# SCH___2022-10-11.net
KiCad netlist of a schematic drawn in EasyEDA
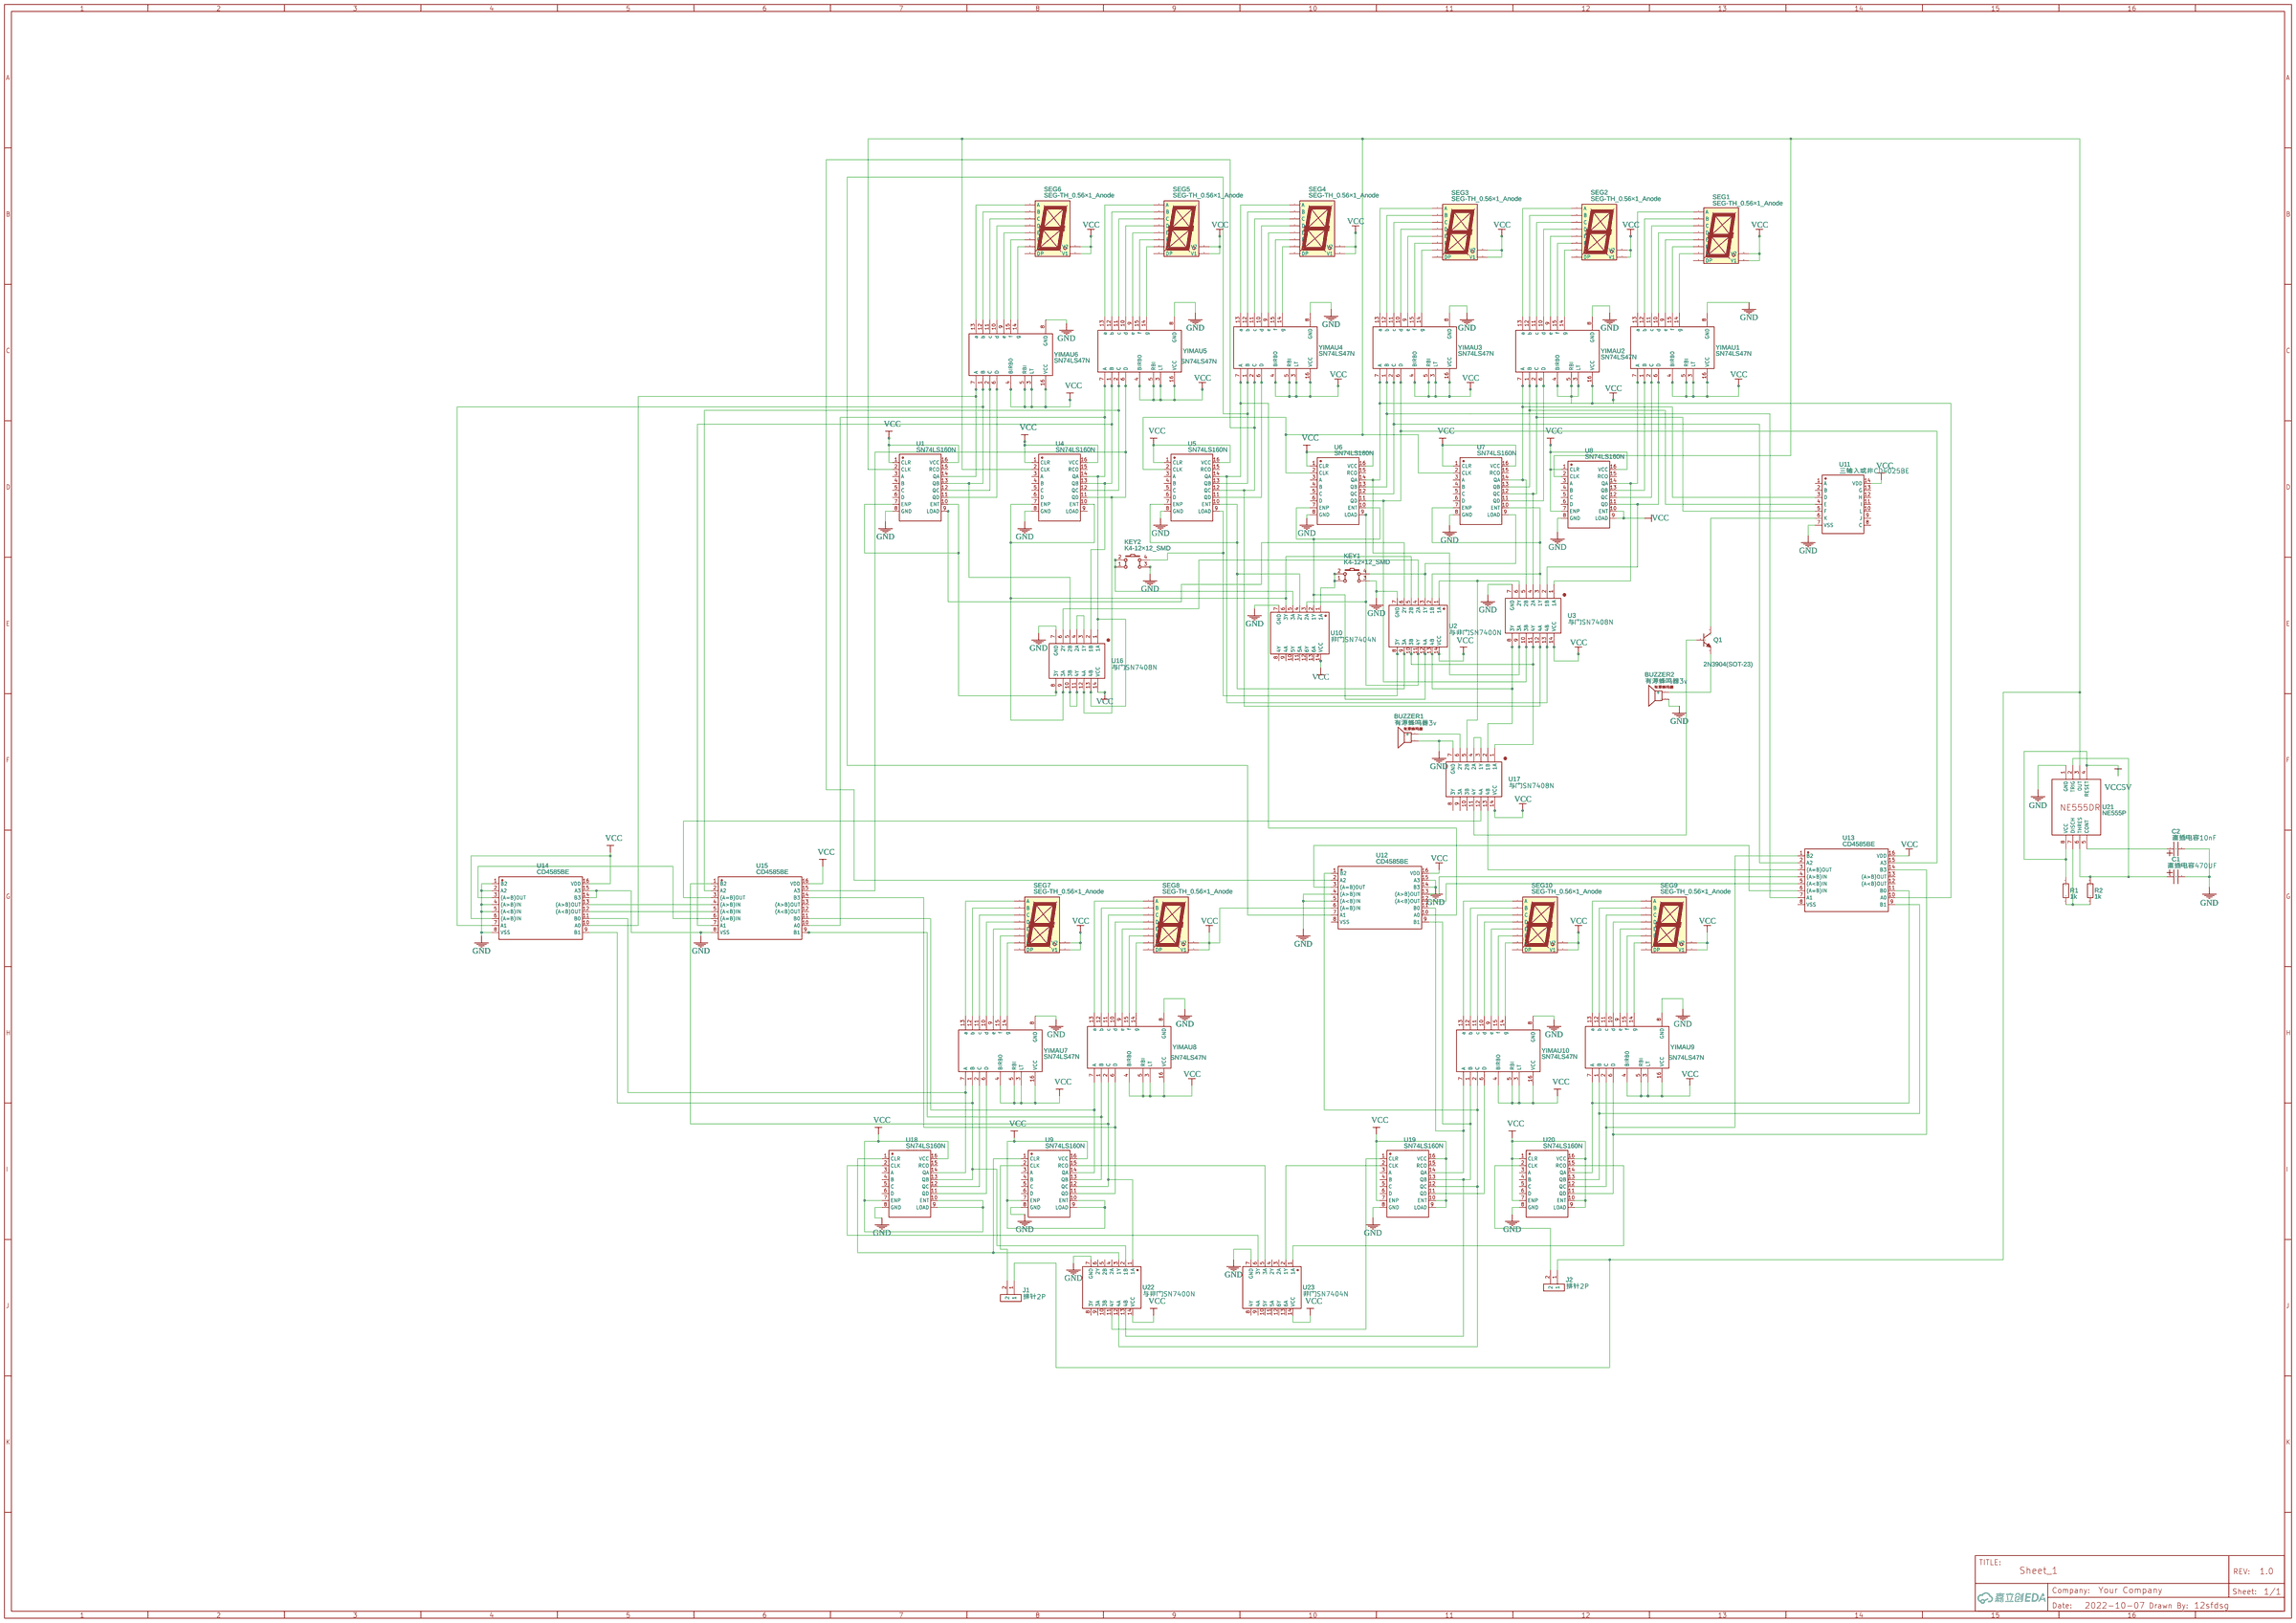
[diagram p0: schematic sheet]

(export (version "E")
  (design (tool "Eeschema 10.0.6"))
  (components
    (comp (ref "BUZZER1")
      (value "有源蜂鸣器3v")
      (fields (field (name "BOM_Manufacturer Part") "TMB12A12") (field (name "BOM_Supplier Part") "C96079"))
      (libsource (lib "") (part "有源蜂鸣器3v"))
    )
    (comp (ref "BUZZER2")
      (value "有源蜂鸣器3v")
      (fields (field (name "BOM_Manufacturer Part") "TMB12A12") (field (name "BOM_Supplier Part") "C96079"))
      (libsource (lib "") (part "有源蜂鸣器3v"))
    )
    (comp (ref "C1") (value "直插电容470UF") (libsource (lib "") (part "直插电容470UF")))
    (comp (ref "C2") (value "直插电容10nF") (libsource (lib "") (part "直插电容470UF_1")))
    (comp (ref "J1") (value "排针2P") (libsource (lib "") (part "排针2P")))
    (comp (ref "J2") (value "排针2P") (libsource (lib "") (part "排针2P")))
    (comp (ref "KEY1")
      (value "K4-12×12_SMD")
      (fields
        (field (name "BOM_Manufacturer Part") "K2-1103SP-E4SW-04")
        (field (name "BOM_Supplier Part") "C136697")
      )
      (libsource (lib "") (part "K4-12×12_SMD"))
    )
    (comp (ref "KEY2")
      (value "K4-12×12_SMD")
      (fields
        (field (name "BOM_Manufacturer Part") "K2-1103SP-E4SW-04")
        (field (name "BOM_Supplier Part") "C136697")
      )
      (libsource (lib "") (part "K4-12×12_SMD"))
    )
    (comp (ref "Q1")
      (value "2N3904(SOT-23)")
      (fields
        (field (name "BOM_Manufacturer Part") "2n3904S-RTK/PS")
        (field (name "BOM_Supplier Part") "C18536")
      )
      (libsource (lib "") (part "2N3904(SOT-23)"))
    )
    (comp (ref "R1")
      (value "1k")
      (fields
        (field (name "BOM_Manufacturer Part") "CFR0W4J0681A50")
        (field (name "BOM_Supplier Part") "C70784")
      )
      (libsource (lib "") (part "直插电阻"))
    )
    (comp (ref "R2")
      (value "1k")
      (fields
        (field (name "BOM_Manufacturer Part") "CFR0W4J0681A50")
        (field (name "BOM_Supplier Part") "C70784")
      )
      (libsource (lib "") (part "直插电阻"))
    )
    (comp (ref "SEG1")
      (value "SEG-TH_0.56×1_Anode")
      (fields (field (name "BOM_Supplier Part") "C8092"))
      (libsource (lib "") (part "SEG-TH_0.56×1_Anode"))
    )
    (comp (ref "SEG2")
      (value "SEG-TH_0.56×1_Anode")
      (fields (field (name "BOM_Supplier Part") "C8092"))
      (libsource (lib "") (part "SEG-TH_0.56×1_Anode"))
    )
    (comp (ref "SEG3")
      (value "SEG-TH_0.56×1_Anode")
      (fields (field (name "BOM_Supplier Part") "C8092"))
      (libsource (lib "") (part "SEG-TH_0.56×1_Anode"))
    )
    (comp (ref "SEG4")
      (value "SEG-TH_0.56×1_Anode")
      (fields (field (name "BOM_Supplier Part") "C8092"))
      (libsource (lib "") (part "SEG-TH_0.56×1_Anode"))
    )
    (comp (ref "SEG5")
      (value "SEG-TH_0.56×1_Anode")
      (fields (field (name "BOM_Supplier Part") "C8092"))
      (libsource (lib "") (part "SEG-TH_0.56×1_Anode"))
    )
    (comp (ref "SEG6")
      (value "SEG-TH_0.56×1_Anode")
      (fields (field (name "BOM_Supplier Part") "C8092"))
      (libsource (lib "") (part "SEG-TH_0.56×1_Anode"))
    )
    (comp (ref "SEG7")
      (value "SEG-TH_0.56×1_Anode")
      (fields (field (name "BOM_Supplier Part") "C8092"))
      (libsource (lib "") (part "SEG-TH_0.56×1_Anode"))
    )
    (comp (ref "SEG8")
      (value "SEG-TH_0.56×1_Anode")
      (fields (field (name "BOM_Supplier Part") "C8092"))
      (libsource (lib "") (part "SEG-TH_0.56×1_Anode"))
    )
    (comp (ref "SEG9")
      (value "SEG-TH_0.56×1_Anode")
      (fields (field (name "BOM_Supplier Part") "C8092"))
      (libsource (lib "") (part "SEG-TH_0.56×1_Anode"))
    )
    (comp (ref "SEG10")
      (value "SEG-TH_0.56×1_Anode")
      (fields (field (name "BOM_Supplier Part") "C8092"))
      (libsource (lib "") (part "SEG-TH_0.56×1_Anode"))
    )
    (comp (ref "U1")
      (value "SN74LS160N")
      (fields
        (field (name "BOM_Manufacturer Part") "CC0805JRNPO9BN821")
        (field (name "BOM_Supplier Part") "C113834")
      )
      (libsource (lib "") (part "SN74LS160N"))
    )
    (comp (ref "U2") (value "与非门SN7400N") (libsource (lib "") (part "SN7400N")))
    (comp (ref "U3") (value "与门SN7408N") (libsource (lib "") (part "SN7408N")))
    (comp (ref "U4")
      (value "SN74LS160N")
      (fields
        (field (name "BOM_Manufacturer Part") "CC0805JRNPO9BN821")
        (field (name "BOM_Supplier Part") "C113834")
      )
      (libsource (lib "") (part "SN74LS160N"))
    )
    (comp (ref "U5")
      (value "SN74LS160N")
      (fields
        (field (name "BOM_Manufacturer Part") "CC0805JRNPO9BN821")
        (field (name "BOM_Supplier Part") "C113834")
      )
      (libsource (lib "") (part "SN74LS160N"))
    )
    (comp (ref "U6")
      (value "SN74LS160N")
      (fields
        (field (name "BOM_Manufacturer Part") "CC0805JRNPO9BN821")
        (field (name "BOM_Supplier Part") "C113834")
      )
      (libsource (lib "") (part "SN74LS160N"))
    )
    (comp (ref "U7")
      (value "SN74LS160N")
      (fields
        (field (name "BOM_Manufacturer Part") "CC0805JRNPO9BN821")
        (field (name "BOM_Supplier Part") "C113834")
      )
      (libsource (lib "") (part "SN74LS160N"))
    )
    (comp (ref "U8")
      (value "SN74LS160N")
      (fields
        (field (name "BOM_Manufacturer Part") "CC0805JRNPO9BN821")
        (field (name "BOM_Supplier Part") "C113834")
      )
      (libsource (lib "") (part "SN74LS160N"))
    )
    (comp (ref "U9")
      (value "SN74LS160N")
      (fields
        (field (name "BOM_Manufacturer Part") "CC0805JRNPO9BN821")
        (field (name "BOM_Supplier Part") "C113834")
      )
      (libsource (lib "") (part "SN74LS160N"))
    )
    (comp (ref "U10") (value "非门SN7404N") (libsource (lib "") (part "SN7404N")))
    (comp (ref "U11")
      (value "三输入或非CD4025BE")
      (fields (field (name "BOM_Manufacturer Part") "CD4025BE") (field (name "BOM_Supplier Part") "C28214"))
      (libsource (lib "") (part "CD4025BE"))
    )
    (comp (ref "U12")
      (value "CD4585BE")
      (fields (field (name "BOM_Supplier Part") "C31466"))
      (libsource (lib "") (part "CD4585BE"))
    )
    (comp (ref "U13")
      (value "CD4585BE")
      (fields (field (name "BOM_Supplier Part") "C31466"))
      (libsource (lib "") (part "CD4585BE"))
    )
    (comp (ref "U14")
      (value "CD4585BE")
      (fields (field (name "BOM_Supplier Part") "C31466"))
      (libsource (lib "") (part "CD4585BE"))
    )
    (comp (ref "U15")
      (value "CD4585BE")
      (fields (field (name "BOM_Supplier Part") "C31466"))
      (libsource (lib "") (part "CD4585BE"))
    )
    (comp (ref "U16") (value "与门SN7408N") (libsource (lib "") (part "SN7408N")))
    (comp (ref "U17") (value "与门SN7408N") (libsource (lib "") (part "SN7408N")))
    (comp (ref "U18")
      (value "SN74LS160N")
      (fields
        (field (name "BOM_Manufacturer Part") "CC0805JRNPO9BN821")
        (field (name "BOM_Supplier Part") "C113834")
      )
      (libsource (lib "") (part "SN74LS160N"))
    )
    (comp (ref "U19")
      (value "SN74LS160N")
      (fields
        (field (name "BOM_Manufacturer Part") "CC0805JRNPO9BN821")
        (field (name "BOM_Supplier Part") "C113834")
      )
      (libsource (lib "") (part "SN74LS160N"))
    )
    (comp (ref "U20")
      (value "SN74LS160N")
      (fields
        (field (name "BOM_Manufacturer Part") "CC0805JRNPO9BN821")
        (field (name "BOM_Supplier Part") "C113834")
      )
      (libsource (lib "") (part "SN74LS160N"))
    )
    (comp (ref "U21") (value "NE555P") (libsource (lib "") (part "NE555P")))
    (comp (ref "U22") (value "与非门SN7400N") (libsource (lib "") (part "SN7400N")))
    (comp (ref "U23") (value "非门SN7404N") (libsource (lib "") (part "SN7404N")))
    (comp (ref "YIMAU1")
      (value "SN74LS47N")
      (fields (field (name "BOM_Supplier Part") "C129379"))
      (libsource (lib "") (part "Unknown_2395_-1825"))
    )
    (comp (ref "YIMAU2")
      (value "SN74LS47N")
      (fields (field (name "BOM_Supplier Part") "C129379"))
      (libsource (lib "") (part "Unknown_2230_-1820"))
    )
    (comp (ref "YIMAU3")
      (value "SN74LS47N")
      (fields (field (name "BOM_Supplier Part") "C129379"))
      (libsource (lib "") (part "Unknown_2025_-1825"))
    )
    (comp (ref "YIMAU4")
      (value "SN74LS47N")
      (fields (field (name "BOM_Supplier Part") "C129379"))
      (libsource (lib "") (part "Unknown_1825_-1825"))
    )
    (comp (ref "YIMAU5")
      (value "SN74LS47N")
      (fields (field (name "BOM_Supplier Part") "C129379"))
      (libsource (lib "") (part "Unknown_1630_-1820"))
    )
    (comp (ref "YIMAU6")
      (value "SN74LS47N")
      (fields (field (name "BOM_Supplier Part") "C129379"))
      (libsource (lib "") (part "Unknown_1445_-1815"))
    )
    (comp (ref "YIMAU7")
      (value "SN74LS47N")
      (fields (field (name "BOM_Supplier Part") "C129379"))
      (libsource (lib "") (part "Unknown_1430_-815"))
    )
    (comp (ref "YIMAU8")
      (value "SN74LS47N")
      (fields (field (name "BOM_Supplier Part") "C129379"))
      (libsource (lib "") (part "Unknown_1615_-820"))
    )
    (comp (ref "YIMAU9")
      (value "SN74LS47N")
      (fields (field (name "BOM_Supplier Part") "C129379"))
      (libsource (lib "") (part "Unknown_2330_-820"))
    )
    (comp (ref "YIMAU10")
      (value "SN74LS47N")
      (fields (field (name "BOM_Supplier Part") "C129379"))
      (libsource (lib "") (part "Unknown_2145_-815"))
    )
  )
  (nets
    (net (code "1") (name "GND") (class "Default")
      (node (ref "BUZZER1") (pin "-") (pinfunction "-_-") (pintype "unspecified"))
      (node (ref "BUZZER2") (pin "-") (pinfunction "-_-") (pintype "unspecified"))
      (node (ref "C1") (pin "2") (pinfunction "2_2") (pintype "unspecified"))
      (node (ref "C2") (pin "2") (pinfunction "2_2") (pintype "unspecified"))
      (node (ref "KEY1") (pin "3") (pinfunction "3_3") (pintype "unspecified"))
      (node (ref "KEY2") (pin "3") (pinfunction "3_3") (pintype "unspecified"))
      (node (ref "U1") (pin "8") (pinfunction "GND_8") (pintype "unspecified"))
      (node (ref "U10") (pin "7") (pinfunction "GND_7") (pintype "unspecified"))
      (node (ref "U11") (pin "7") (pinfunction "VSS_7") (pintype "unspecified"))
      (node (ref "U12") (pin "14") (pinfunction "B3_14") (pintype "unspecified"))
      (node (ref "U12") (pin "15") (pinfunction "A3_15") (pintype "unspecified"))
      (node (ref "U12") (pin "4") (pinfunction "(A>B)IN_4") (pintype "unspecified"))
      (node (ref "U12") (pin "5") (pinfunction "(A<B)IN_5") (pintype "unspecified"))
      (node (ref "U14") (pin "1") (pinfunction "B2_1") (pintype "unspecified"))
      (node (ref "U14") (pin "14") (pinfunction "B3_14") (pintype "unspecified"))
      (node (ref "U14") (pin "15") (pinfunction "A3_15") (pintype "unspecified"))
      (node (ref "U14") (pin "2") (pinfunction "A2_2") (pintype "unspecified"))
      (node (ref "U14") (pin "4") (pinfunction "(A>B)IN_4") (pintype "unspecified"))
      (node (ref "U14") (pin "5") (pinfunction "(A<B)IN_5") (pintype "unspecified"))
      (node (ref "U14") (pin "8") (pinfunction "VSS_8") (pintype "unspecified"))
      (node (ref "U15") (pin "8") (pinfunction "VSS_8") (pintype "unspecified"))
      (node (ref "U16") (pin "7") (pinfunction "GND_7") (pintype "unspecified"))
      (node (ref "U17") (pin "7") (pinfunction "GND_7") (pintype "unspecified"))
      (node (ref "U18") (pin "8") (pinfunction "GND_8") (pintype "unspecified"))
      (node (ref "U19") (pin "8") (pinfunction "GND_8") (pintype "unspecified"))
      (node (ref "U2") (pin "7") (pinfunction "GND_7") (pintype "unspecified"))
      (node (ref "U20") (pin "8") (pinfunction "GND_8") (pintype "unspecified"))
      (node (ref "U21") (pin "1") (pinfunction "GND_1") (pintype "unspecified"))
      (node (ref "U22") (pin "7") (pinfunction "GND_7") (pintype "unspecified"))
      (node (ref "U23") (pin "7") (pinfunction "GND_7") (pintype "unspecified"))
      (node (ref "U3") (pin "7") (pinfunction "GND_7") (pintype "unspecified"))
      (node (ref "U4") (pin "8") (pinfunction "GND_8") (pintype "unspecified"))
      (node (ref "U5") (pin "8") (pinfunction "GND_8") (pintype "unspecified"))
      (node (ref "U6") (pin "8") (pinfunction "GND_8") (pintype "unspecified"))
      (node (ref "U7") (pin "8") (pinfunction "GND_8") (pintype "unspecified"))
      (node (ref "U8") (pin "8") (pinfunction "GND_8") (pintype "unspecified"))
      (node (ref "U9") (pin "8") (pinfunction "GND_8") (pintype "unspecified"))
      (node (ref "YIMAU1") (pin "8") (pinfunction "GND_8") (pintype "passive"))
      (node (ref "YIMAU10") (pin "8") (pinfunction "GND_8") (pintype "passive"))
      (node (ref "YIMAU2") (pin "8") (pinfunction "GND_8") (pintype "passive"))
      (node (ref "YIMAU3") (pin "8") (pinfunction "GND_8") (pintype "passive"))
      (node (ref "YIMAU4") (pin "8") (pinfunction "GND_8") (pintype "passive"))
      (node (ref "YIMAU5") (pin "8") (pinfunction "GND_8") (pintype "passive"))
      (node (ref "YIMAU6") (pin "8") (pinfunction "GND_8") (pintype "passive"))
      (node (ref "YIMAU7") (pin "8") (pinfunction "GND_8") (pintype "passive"))
      (node (ref "YIMAU8") (pin "8") (pinfunction "GND_8") (pintype "passive"))
      (node (ref "YIMAU9") (pin "8") (pinfunction "GND_8") (pintype "passive"))
    )
    (net (code "2") (name "Net-(Q1-B)") (class "Default")
      (node (ref "Q1") (pin "2") (pinfunction "B_2") (pintype "input"))
      (node (ref "U17") (pin "11") (pinfunction "4Y_11") (pintype "unspecified"))
    )
    (net (code "3") (name "Net-(Q1-C)") (class "Default")
      (node (ref "Q1") (pin "3") (pinfunction "C_3") (pintype "input"))
      (node (ref "U11") (pin "6") (pinfunction "K_6") (pintype "unspecified"))
    )
    (net (code "4") (name "Net-(Q1-E)") (class "Default")
      (node (ref "BUZZER2") (pin "+") (pinfunction "+_+") (pintype "unspecified"))
      (node (ref "Q1") (pin "1") (pinfunction "E_1") (pintype "input"))
    )
    (net (code "5") (name "Net-(SEG1-A)") (class "Default")
      (node (ref "SEG1") (pin "7") (pinfunction "A_7") (pintype "unspecified"))
      (node (ref "YIMAU1") (pin "13") (pinfunction "a_13") (pintype "unspecified"))
    )
    (net (code "6") (name "Net-(SEG1-B)") (class "Default")
      (node (ref "SEG1") (pin "6") (pinfunction "B_6") (pintype "unspecified"))
      (node (ref "YIMAU1") (pin "12") (pinfunction "b_12") (pintype "unspecified"))
    )
    (net (code "7") (name "Net-(SEG1-C)") (class "Default")
      (node (ref "SEG1") (pin "4") (pinfunction "C_4") (pintype "unspecified"))
      (node (ref "YIMAU1") (pin "11") (pinfunction "c_11") (pintype "unspecified"))
    )
    (net (code "8") (name "Net-(SEG1-D)") (class "Default")
      (node (ref "SEG1") (pin "2") (pinfunction "D_2") (pintype "unspecified"))
      (node (ref "YIMAU1") (pin "10") (pinfunction "d_10") (pintype "unspecified"))
    )
    (net (code "9") (name "Net-(SEG1-E)") (class "Default")
      (node (ref "SEG1") (pin "1") (pinfunction "E_1") (pintype "unspecified"))
      (node (ref "YIMAU1") (pin "9") (pinfunction "e_9") (pintype "unspecified"))
    )
    (net (code "10") (name "Net-(SEG1-F)") (class "Default")
      (node (ref "SEG1") (pin "9") (pinfunction "F_9") (pintype "unspecified"))
      (node (ref "YIMAU1") (pin "15") (pinfunction "f_15") (pintype "unspecified"))
    )
    (net (code "11") (name "Net-(SEG1-G)") (class "Default")
      (node (ref "SEG1") (pin "10") (pinfunction "G_10") (pintype "unspecified"))
      (node (ref "YIMAU1") (pin "14") (pinfunction "g_14") (pintype "unspecified"))
    )
    (net (code "12") (name "Net-(SEG2-A)") (class "Default")
      (node (ref "SEG2") (pin "7") (pinfunction "A_7") (pintype "unspecified"))
      (node (ref "YIMAU2") (pin "13") (pinfunction "a_13") (pintype "unspecified"))
    )
    (net (code "13") (name "Net-(SEG2-B)") (class "Default")
      (node (ref "SEG2") (pin "6") (pinfunction "B_6") (pintype "unspecified"))
      (node (ref "YIMAU2") (pin "12") (pinfunction "b_12") (pintype "unspecified"))
    )
    (net (code "14") (name "Net-(SEG2-C)") (class "Default")
      (node (ref "SEG2") (pin "4") (pinfunction "C_4") (pintype "unspecified"))
      (node (ref "YIMAU2") (pin "11") (pinfunction "c_11") (pintype "unspecified"))
    )
    (net (code "15") (name "Net-(SEG2-D)") (class "Default")
      (node (ref "SEG2") (pin "2") (pinfunction "D_2") (pintype "unspecified"))
      (node (ref "YIMAU2") (pin "10") (pinfunction "d_10") (pintype "unspecified"))
    )
    (net (code "16") (name "Net-(SEG2-E)") (class "Default")
      (node (ref "SEG2") (pin "1") (pinfunction "E_1") (pintype "unspecified"))
      (node (ref "YIMAU2") (pin "9") (pinfunction "e_9") (pintype "unspecified"))
    )
    (net (code "17") (name "Net-(SEG2-F)") (class "Default")
      (node (ref "SEG2") (pin "9") (pinfunction "F_9") (pintype "unspecified"))
      (node (ref "YIMAU2") (pin "15") (pinfunction "f_15") (pintype "unspecified"))
    )
    (net (code "18") (name "Net-(SEG2-G)") (class "Default")
      (node (ref "SEG2") (pin "10") (pinfunction "G_10") (pintype "unspecified"))
      (node (ref "YIMAU2") (pin "14") (pinfunction "g_14") (pintype "unspecified"))
    )
    (net (code "19") (name "Net-(SEG3-A)") (class "Default")
      (node (ref "SEG3") (pin "7") (pinfunction "A_7") (pintype "unspecified"))
      (node (ref "YIMAU3") (pin "13") (pinfunction "a_13") (pintype "unspecified"))
    )
    (net (code "20") (name "Net-(SEG3-B)") (class "Default")
      (node (ref "SEG3") (pin "6") (pinfunction "B_6") (pintype "unspecified"))
      (node (ref "YIMAU3") (pin "12") (pinfunction "b_12") (pintype "unspecified"))
    )
    (net (code "21") (name "Net-(SEG3-C)") (class "Default")
      (node (ref "SEG3") (pin "4") (pinfunction "C_4") (pintype "unspecified"))
      (node (ref "YIMAU3") (pin "11") (pinfunction "c_11") (pintype "unspecified"))
    )
    (net (code "22") (name "Net-(SEG3-D)") (class "Default")
      (node (ref "SEG3") (pin "2") (pinfunction "D_2") (pintype "unspecified"))
      (node (ref "YIMAU3") (pin "10") (pinfunction "d_10") (pintype "unspecified"))
    )
    (net (code "23") (name "Net-(SEG3-E)") (class "Default")
      (node (ref "SEG3") (pin "1") (pinfunction "E_1") (pintype "unspecified"))
      (node (ref "YIMAU3") (pin "9") (pinfunction "e_9") (pintype "unspecified"))
    )
    (net (code "24") (name "Net-(SEG3-F)") (class "Default")
      (node (ref "SEG3") (pin "9") (pinfunction "F_9") (pintype "unspecified"))
      (node (ref "YIMAU3") (pin "15") (pinfunction "f_15") (pintype "unspecified"))
    )
    (net (code "25") (name "Net-(SEG3-G)") (class "Default")
      (node (ref "SEG3") (pin "10") (pinfunction "G_10") (pintype "unspecified"))
      (node (ref "YIMAU3") (pin "14") (pinfunction "g_14") (pintype "unspecified"))
    )
    (net (code "26") (name "Net-(SEG4-A)") (class "Default")
      (node (ref "SEG4") (pin "7") (pinfunction "A_7") (pintype "unspecified"))
      (node (ref "YIMAU4") (pin "13") (pinfunction "a_13") (pintype "unspecified"))
    )
    (net (code "27") (name "Net-(SEG4-B)") (class "Default")
      (node (ref "SEG4") (pin "6") (pinfunction "B_6") (pintype "unspecified"))
      (node (ref "YIMAU4") (pin "12") (pinfunction "b_12") (pintype "unspecified"))
    )
    (net (code "28") (name "Net-(SEG4-C)") (class "Default")
      (node (ref "SEG4") (pin "4") (pinfunction "C_4") (pintype "unspecified"))
      (node (ref "YIMAU4") (pin "11") (pinfunction "c_11") (pintype "unspecified"))
    )
    (net (code "29") (name "Net-(SEG4-D)") (class "Default")
      (node (ref "SEG4") (pin "2") (pinfunction "D_2") (pintype "unspecified"))
      (node (ref "YIMAU4") (pin "10") (pinfunction "d_10") (pintype "unspecified"))
    )
    (net (code "30") (name "Net-(SEG4-E)") (class "Default")
      (node (ref "SEG4") (pin "1") (pinfunction "E_1") (pintype "unspecified"))
      (node (ref "YIMAU4") (pin "9") (pinfunction "e_9") (pintype "unspecified"))
    )
    (net (code "31") (name "Net-(SEG4-F)") (class "Default")
      (node (ref "SEG4") (pin "9") (pinfunction "F_9") (pintype "unspecified"))
      (node (ref "YIMAU4") (pin "15") (pinfunction "f_15") (pintype "unspecified"))
    )
    (net (code "32") (name "Net-(SEG4-G)") (class "Default")
      (node (ref "SEG4") (pin "10") (pinfunction "G_10") (pintype "unspecified"))
      (node (ref "YIMAU4") (pin "14") (pinfunction "g_14") (pintype "unspecified"))
    )
    (net (code "33") (name "Net-(SEG5-A)") (class "Default")
      (node (ref "SEG5") (pin "7") (pinfunction "A_7") (pintype "unspecified"))
      (node (ref "YIMAU5") (pin "13") (pinfunction "a_13") (pintype "unspecified"))
    )
    (net (code "34") (name "Net-(SEG5-B)") (class "Default")
      (node (ref "SEG5") (pin "6") (pinfunction "B_6") (pintype "unspecified"))
      (node (ref "YIMAU5") (pin "12") (pinfunction "b_12") (pintype "unspecified"))
    )
    (net (code "35") (name "Net-(SEG5-C)") (class "Default")
      (node (ref "SEG5") (pin "4") (pinfunction "C_4") (pintype "unspecified"))
      (node (ref "YIMAU5") (pin "11") (pinfunction "c_11") (pintype "unspecified"))
    )
    (net (code "36") (name "Net-(SEG5-D)") (class "Default")
      (node (ref "SEG5") (pin "2") (pinfunction "D_2") (pintype "unspecified"))
      (node (ref "YIMAU5") (pin "10") (pinfunction "d_10") (pintype "unspecified"))
    )
    (net (code "37") (name "Net-(SEG5-E)") (class "Default")
      (node (ref "SEG5") (pin "1") (pinfunction "E_1") (pintype "unspecified"))
      (node (ref "YIMAU5") (pin "9") (pinfunction "e_9") (pintype "unspecified"))
    )
    (net (code "38") (name "Net-(SEG5-F)") (class "Default")
      (node (ref "SEG5") (pin "9") (pinfunction "F_9") (pintype "unspecified"))
      (node (ref "YIMAU5") (pin "15") (pinfunction "f_15") (pintype "unspecified"))
    )
    (net (code "39") (name "Net-(SEG5-G)") (class "Default")
      (node (ref "SEG5") (pin "10") (pinfunction "G_10") (pintype "unspecified"))
      (node (ref "YIMAU5") (pin "14") (pinfunction "g_14") (pintype "unspecified"))
    )
    (net (code "40") (name "Net-(SEG6-A)") (class "Default")
      (node (ref "SEG6") (pin "7") (pinfunction "A_7") (pintype "unspecified"))
      (node (ref "YIMAU6") (pin "13") (pinfunction "a_13") (pintype "unspecified"))
    )
    (net (code "41") (name "Net-(SEG6-B)") (class "Default")
      (node (ref "SEG6") (pin "6") (pinfunction "B_6") (pintype "unspecified"))
      (node (ref "YIMAU6") (pin "12") (pinfunction "b_12") (pintype "unspecified"))
    )
    (net (code "42") (name "Net-(SEG6-C)") (class "Default")
      (node (ref "SEG6") (pin "4") (pinfunction "C_4") (pintype "unspecified"))
      (node (ref "YIMAU6") (pin "11") (pinfunction "c_11") (pintype "unspecified"))
    )
    (net (code "43") (name "Net-(SEG6-D)") (class "Default")
      (node (ref "SEG6") (pin "2") (pinfunction "D_2") (pintype "unspecified"))
      (node (ref "YIMAU6") (pin "10") (pinfunction "d_10") (pintype "unspecified"))
    )
    (net (code "44") (name "Net-(SEG6-E)") (class "Default")
      (node (ref "SEG6") (pin "1") (pinfunction "E_1") (pintype "unspecified"))
      (node (ref "YIMAU6") (pin "9") (pinfunction "e_9") (pintype "unspecified"))
    )
    (net (code "45") (name "Net-(SEG6-F)") (class "Default")
      (node (ref "SEG6") (pin "9") (pinfunction "F_9") (pintype "unspecified"))
      (node (ref "YIMAU6") (pin "15") (pinfunction "f_15") (pintype "unspecified"))
    )
    (net (code "46") (name "Net-(SEG6-G)") (class "Default")
      (node (ref "SEG6") (pin "10") (pinfunction "G_10") (pintype "unspecified"))
      (node (ref "YIMAU6") (pin "14") (pinfunction "g_14") (pintype "unspecified"))
    )
    (net (code "47") (name "Net-(SEG7-A)") (class "Default")
      (node (ref "SEG7") (pin "7") (pinfunction "A_7") (pintype "unspecified"))
      (node (ref "YIMAU7") (pin "13") (pinfunction "a_13") (pintype "unspecified"))
    )
    (net (code "48") (name "Net-(SEG7-B)") (class "Default")
      (node (ref "SEG7") (pin "6") (pinfunction "B_6") (pintype "unspecified"))
      (node (ref "YIMAU7") (pin "12") (pinfunction "b_12") (pintype "unspecified"))
    )
    (net (code "49") (name "Net-(SEG7-C)") (class "Default")
      (node (ref "SEG7") (pin "4") (pinfunction "C_4") (pintype "unspecified"))
      (node (ref "YIMAU7") (pin "11") (pinfunction "c_11") (pintype "unspecified"))
    )
    (net (code "50") (name "Net-(SEG7-D)") (class "Default")
      (node (ref "SEG7") (pin "2") (pinfunction "D_2") (pintype "unspecified"))
      (node (ref "YIMAU7") (pin "10") (pinfunction "d_10") (pintype "unspecified"))
    )
    (net (code "51") (name "Net-(SEG7-E)") (class "Default")
      (node (ref "SEG7") (pin "1") (pinfunction "E_1") (pintype "unspecified"))
      (node (ref "YIMAU7") (pin "9") (pinfunction "e_9") (pintype "unspecified"))
    )
    (net (code "52") (name "Net-(SEG7-F)") (class "Default")
      (node (ref "SEG7") (pin "9") (pinfunction "F_9") (pintype "unspecified"))
      (node (ref "YIMAU7") (pin "15") (pinfunction "f_15") (pintype "unspecified"))
    )
    (net (code "53") (name "Net-(SEG7-G)") (class "Default")
      (node (ref "SEG7") (pin "10") (pinfunction "G_10") (pintype "unspecified"))
      (node (ref "YIMAU7") (pin "14") (pinfunction "g_14") (pintype "unspecified"))
    )
    (net (code "54") (name "Net-(SEG8-A)") (class "Default")
      (node (ref "SEG8") (pin "7") (pinfunction "A_7") (pintype "unspecified"))
      (node (ref "YIMAU8") (pin "13") (pinfunction "a_13") (pintype "unspecified"))
    )
    (net (code "55") (name "Net-(SEG8-B)") (class "Default")
      (node (ref "SEG8") (pin "6") (pinfunction "B_6") (pintype "unspecified"))
      (node (ref "YIMAU8") (pin "12") (pinfunction "b_12") (pintype "unspecified"))
    )
    (net (code "56") (name "Net-(SEG8-C)") (class "Default")
      (node (ref "SEG8") (pin "4") (pinfunction "C_4") (pintype "unspecified"))
      (node (ref "YIMAU8") (pin "11") (pinfunction "c_11") (pintype "unspecified"))
    )
    (net (code "57") (name "Net-(SEG8-D)") (class "Default")
      (node (ref "SEG8") (pin "2") (pinfunction "D_2") (pintype "unspecified"))
      (node (ref "YIMAU8") (pin "10") (pinfunction "d_10") (pintype "unspecified"))
    )
    (net (code "58") (name "Net-(SEG8-E)") (class "Default")
      (node (ref "SEG8") (pin "1") (pinfunction "E_1") (pintype "unspecified"))
      (node (ref "YIMAU8") (pin "9") (pinfunction "e_9") (pintype "unspecified"))
    )
    (net (code "59") (name "Net-(SEG8-F)") (class "Default")
      (node (ref "SEG8") (pin "9") (pinfunction "F_9") (pintype "unspecified"))
      (node (ref "YIMAU8") (pin "15") (pinfunction "f_15") (pintype "unspecified"))
    )
    (net (code "60") (name "Net-(SEG8-G)") (class "Default")
      (node (ref "SEG8") (pin "10") (pinfunction "G_10") (pintype "unspecified"))
      (node (ref "YIMAU8") (pin "14") (pinfunction "g_14") (pintype "unspecified"))
    )
    (net (code "61") (name "Net-(SEG9-A)") (class "Default")
      (node (ref "SEG9") (pin "7") (pinfunction "A_7") (pintype "unspecified"))
      (node (ref "YIMAU9") (pin "13") (pinfunction "a_13") (pintype "unspecified"))
    )
    (net (code "62") (name "Net-(SEG9-B)") (class "Default")
      (node (ref "SEG9") (pin "6") (pinfunction "B_6") (pintype "unspecified"))
      (node (ref "YIMAU9") (pin "12") (pinfunction "b_12") (pintype "unspecified"))
    )
    (net (code "63") (name "Net-(SEG9-C)") (class "Default")
      (node (ref "SEG9") (pin "4") (pinfunction "C_4") (pintype "unspecified"))
      (node (ref "YIMAU9") (pin "11") (pinfunction "c_11") (pintype "unspecified"))
    )
    (net (code "64") (name "Net-(SEG9-D)") (class "Default")
      (node (ref "SEG9") (pin "2") (pinfunction "D_2") (pintype "unspecified"))
      (node (ref "YIMAU9") (pin "10") (pinfunction "d_10") (pintype "unspecified"))
    )
    (net (code "65") (name "Net-(SEG9-E)") (class "Default")
      (node (ref "SEG9") (pin "1") (pinfunction "E_1") (pintype "unspecified"))
      (node (ref "YIMAU9") (pin "9") (pinfunction "e_9") (pintype "unspecified"))
    )
    (net (code "66") (name "Net-(SEG9-F)") (class "Default")
      (node (ref "SEG9") (pin "9") (pinfunction "F_9") (pintype "unspecified"))
      (node (ref "YIMAU9") (pin "15") (pinfunction "f_15") (pintype "unspecified"))
    )
    (net (code "67") (name "Net-(SEG9-G)") (class "Default")
      (node (ref "SEG9") (pin "10") (pinfunction "G_10") (pintype "unspecified"))
      (node (ref "YIMAU9") (pin "14") (pinfunction "g_14") (pintype "unspecified"))
    )
    (net (code "68") (name "Net-(SEG10-A)") (class "Default")
      (node (ref "SEG10") (pin "7") (pinfunction "A_7") (pintype "unspecified"))
      (node (ref "YIMAU10") (pin "13") (pinfunction "a_13") (pintype "unspecified"))
    )
    (net (code "69") (name "Net-(SEG10-B)") (class "Default")
      (node (ref "SEG10") (pin "6") (pinfunction "B_6") (pintype "unspecified"))
      (node (ref "YIMAU10") (pin "12") (pinfunction "b_12") (pintype "unspecified"))
    )
    (net (code "70") (name "Net-(SEG10-C)") (class "Default")
      (node (ref "SEG10") (pin "4") (pinfunction "C_4") (pintype "unspecified"))
      (node (ref "YIMAU10") (pin "11") (pinfunction "c_11") (pintype "unspecified"))
    )
    (net (code "71") (name "Net-(SEG10-D)") (class "Default")
      (node (ref "SEG10") (pin "2") (pinfunction "D_2") (pintype "unspecified"))
      (node (ref "YIMAU10") (pin "10") (pinfunction "d_10") (pintype "unspecified"))
    )
    (net (code "72") (name "Net-(SEG10-E)") (class "Default")
      (node (ref "SEG10") (pin "1") (pinfunction "E_1") (pintype "unspecified"))
      (node (ref "YIMAU10") (pin "9") (pinfunction "e_9") (pintype "unspecified"))
    )
    (net (code "73") (name "Net-(SEG10-F)") (class "Default")
      (node (ref "SEG10") (pin "9") (pinfunction "F_9") (pintype "unspecified"))
      (node (ref "YIMAU10") (pin "15") (pinfunction "f_15") (pintype "unspecified"))
    )
    (net (code "74") (name "Net-(SEG10-G)") (class "Default")
      (node (ref "SEG10") (pin "10") (pinfunction "G_10") (pintype "unspecified"))
      (node (ref "YIMAU10") (pin "14") (pinfunction "g_14") (pintype "unspecified"))
    )
    (net (code "75") (name "Net-(U1-CLK)") (class "Default")
      (node (ref "J1") (pin "1") (pinfunction "1_1") (pintype "unspecified"))
      (node (ref "J2") (pin "1") (pinfunction "1_1") (pintype "unspecified"))
      (node (ref "U1") (pin "2") (pinfunction "CLK_2") (pintype "unspecified"))
      (node (ref "U21") (pin "3") (pinfunction "OUT_3") (pintype "unspecified"))
      (node (ref "U4") (pin "2") (pinfunction "CLK_2") (pintype "unspecified"))
      (node (ref "U5") (pin "2") (pinfunction "CLK_2") (pintype "unspecified"))
      (node (ref "U6") (pin "2") (pinfunction "CLK_2") (pintype "unspecified"))
      (node (ref "U7") (pin "2") (pinfunction "CLK_2") (pintype "unspecified"))
      (node (ref "U8") (pin "2") (pinfunction "CLK_2") (pintype "unspecified"))
    )
    (net (code "76") (name "Net-(U1-ENP)") (class "Default")
      (node (ref "U1") (pin "10") (pinfunction "ENT_10") (pintype "unspecified"))
      (node (ref "U1") (pin "7") (pinfunction "ENP_7") (pintype "unspecified"))
      (node (ref "U16") (pin "8") (pinfunction "3Y_8") (pintype "unspecified"))
    )
    (net (code "77") (name "Net-(U1-LOAD)") (class "Default")
      (node (ref "U1") (pin "9") (pinfunction "LOAD_9") (pintype "unspecified"))
      (node (ref "U2") (pin "6") (pinfunction "2Y_6") (pintype "unspecified"))
    )
    (net (code "78") (name "Net-(U1-QA)") (class "Default")
      (node (ref "U1") (pin "14") (pinfunction "QA_14") (pintype "unspecified"))
      (node (ref "U14") (pin "10") (pinfunction "A0_10") (pintype "unspecified"))
      (node (ref "YIMAU6") (pin "7") (pinfunction "A_7") (pintype "unspecified"))
    )
    (net (code "79") (name "Net-(U1-QB)") (class "Default")
      (node (ref "U1") (pin "13") (pinfunction "QB_13") (pintype "unspecified"))
      (node (ref "U14") (pin "7") (pinfunction "A1_7") (pintype "unspecified"))
      (node (ref "U16") (pin "5") (pinfunction "2B_5") (pintype "unspecified"))
      (node (ref "YIMAU6") (pin "1") (pinfunction "B_1") (pintype "unspecified"))
    )
    (net (code "80") (name "Net-(U1-QC)") (class "Default")
      (node (ref "U1") (pin "12") (pinfunction "QC_12") (pintype "unspecified"))
      (node (ref "YIMAU6") (pin "2") (pinfunction "C_2") (pintype "unspecified"))
    )
    (net (code "81") (name "Net-(U1-QD)") (class "Default")
      (node (ref "U1") (pin "11") (pinfunction "QD_11") (pintype "unspecified"))
      (node (ref "YIMAU6") (pin "6") (pinfunction "D_6") (pintype "unspecified"))
    )
    (net (code "82") (name "Net-(U2-1B)") (class "Default")
      (node (ref "U2") (pin "2") (pinfunction "1B_2") (pintype "unspecified"))
      (node (ref "U3") (pin "3") (pinfunction "1Y_3") (pintype "unspecified"))
      (node (ref "U7") (pin "10") (pinfunction "ENT_10") (pintype "unspecified"))
      (node (ref "U7") (pin "7") (pinfunction "ENP_7") (pintype "unspecified"))
    )
    (net (code "83") (name "Net-(U2-1Y)") (class "Default")
      (node (ref "KEY1") (pin "4") (pinfunction "4_4") (pintype "unspecified"))
      (node (ref "U2") (pin "3") (pinfunction "1Y_3") (pintype "unspecified"))
      (node (ref "U7") (pin "9") (pinfunction "LOAD_9") (pintype "unspecified"))
    )
    (net (code "84") (name "Net-(U2-3Y)") (class "Default")
      (node (ref "KEY2") (pin "4") (pinfunction "4_4") (pintype "unspecified"))
      (node (ref "U2") (pin "8") (pinfunction "3Y_8") (pintype "unspecified"))
      (node (ref "U5") (pin "9") (pinfunction "LOAD_9") (pintype "unspecified"))
    )
    (net (code "85") (name "Net-(U3-1A)") (class "Default")
      (node (ref "U3") (pin "1") (pinfunction "1A_1") (pintype "unspecified"))
      (node (ref "U8") (pin "14") (pinfunction "QA_14") (pintype "unspecified"))
      (node (ref "YIMAU1") (pin "7") (pinfunction "A_7") (pintype "unspecified"))
    )
    (net (code "86") (name "Net-(U3-1B)") (class "Default")
      (node (ref "U3") (pin "2") (pinfunction "1B_2") (pintype "unspecified"))
      (node (ref "U8") (pin "11") (pinfunction "QD_11") (pintype "unspecified"))
      (node (ref "YIMAU1") (pin "6") (pinfunction "D_6") (pintype "unspecified"))
    )
    (net (code "87") (name "Net-(U5-QD)") (class "Default")
      (node (ref "U5") (pin "11") (pinfunction "QD_11") (pintype "unspecified"))
      (node (ref "YIMAU4") (pin "6") (pinfunction "D_6") (pintype "unspecified"))
    )
    (net (code "88") (name "Net-(U7-QD)") (class "Default")
      (node (ref "U7") (pin "11") (pinfunction "QD_11") (pintype "unspecified"))
      (node (ref "YIMAU2") (pin "6") (pinfunction "D_6") (pintype "unspecified"))
    )
    (net (code "89") (name "Net-(U8-QB)") (class "Default")
      (node (ref "U8") (pin "13") (pinfunction "QB_13") (pintype "unspecified"))
      (node (ref "YIMAU1") (pin "1") (pinfunction "B_1") (pintype "unspecified"))
    )
    (net (code "90") (name "Net-(U8-QC)") (class "Default")
      (node (ref "U8") (pin "12") (pinfunction "QC_12") (pintype "unspecified"))
      (node (ref "YIMAU1") (pin "2") (pinfunction "C_2") (pintype "unspecified"))
    )
    (net (code "91") (name "Net-(U9-CLK)") (class "Default")
      (node (ref "J1") (pin "2") (pinfunction "2_2") (pintype "unspecified"))
      (node (ref "U9") (pin "2") (pinfunction "CLK_2") (pintype "unspecified"))
    )
    (net (code "92") (name "Net-(U10-1A)") (class "Default")
      (node (ref "KEY1") (pin "1") (pinfunction "1_1") (pintype "unspecified"))
      (node (ref "KEY1") (pin "2") (pinfunction "2_2") (pintype "unspecified"))
      (node (ref "U10") (pin "1") (pinfunction "1A_1") (pintype "unspecified"))
    )
    (net (code "93") (name "Net-(U10-1Y)") (class "Default")
      (node (ref "U10") (pin "2") (pinfunction "1Y_2") (pintype "unspecified"))
      (node (ref "U2") (pin "12") (pinfunction "4A_12") (pintype "unspecified"))
      (node (ref "U6") (pin "10") (pinfunction "ENT_10") (pintype "unspecified"))
      (node (ref "U6") (pin "7") (pinfunction "ENP_7") (pintype "unspecified"))
    )
    (net (code "94") (name "Net-(U10-2A)") (class "Default")
      (node (ref "U10") (pin "3") (pinfunction "2A_3") (pintype "unspecified"))
      (node (ref "U2") (pin "11") (pinfunction "4Y_11") (pintype "unspecified"))
      (node (ref "U6") (pin "9") (pinfunction "LOAD_9") (pintype "unspecified"))
    )
    (net (code "95") (name "Net-(U10-2Y)") (class "Default")
      (node (ref "U10") (pin "4") (pinfunction "2Y_4") (pintype "unspecified"))
      (node (ref "U2") (pin "9") (pinfunction "3A_9") (pintype "unspecified"))
      (node (ref "U5") (pin "10") (pinfunction "ENT_10") (pintype "unspecified"))
      (node (ref "U5") (pin "7") (pinfunction "ENP_7") (pintype "unspecified"))
    )
    (net (code "96") (name "Net-(U10-3A)") (class "Default")
      (node (ref "KEY2") (pin "1") (pinfunction "1_1") (pintype "unspecified"))
      (node (ref "KEY2") (pin "2") (pinfunction "2_2") (pintype "unspecified"))
      (node (ref "U10") (pin "5") (pinfunction "3A_5") (pintype "unspecified"))
    )
    (net (code "97") (name "Net-(U10-3Y)") (class "Default")
      (node (ref "U10") (pin "6") (pinfunction "3Y_6") (pintype "unspecified"))
      (node (ref "U16") (pin "9") (pinfunction "3A_9") (pintype "unspecified"))
      (node (ref "U2") (pin "5") (pinfunction "2B_5") (pintype "unspecified"))
      (node (ref "U4") (pin "10") (pinfunction "ENT_10") (pintype "unspecified"))
      (node (ref "U4") (pin "7") (pinfunction "ENP_7") (pintype "unspecified"))
    )
    (net (code "98") (name "Net-(U11-D)") (class "Default")
      (node (ref "U11") (pin "3") (pinfunction "D_3") (pintype "unspecified"))
      (node (ref "U3") (pin "5") (pinfunction "2B_5") (pintype "unspecified"))
      (node (ref "U7") (pin "14") (pinfunction "QA_14") (pintype "unspecified"))
      (node (ref "YIMAU2") (pin "7") (pinfunction "A_7") (pintype "unspecified"))
    )
    (net (code "99") (name "Net-(U11-E)") (class "Default")
      (node (ref "U11") (pin "4") (pinfunction "E_4") (pintype "unspecified"))
      (node (ref "U7") (pin "13") (pinfunction "QB_13") (pintype "unspecified"))
      (node (ref "YIMAU2") (pin "1") (pinfunction "B_1") (pintype "unspecified"))
    )
    (net (code "100") (name "Net-(U11-F)") (class "Default")
      (node (ref "U11") (pin "5") (pinfunction "F_5") (pintype "unspecified"))
      (node (ref "U3") (pin "4") (pinfunction "2A_4") (pintype "unspecified"))
      (node (ref "U7") (pin "12") (pinfunction "QC_12") (pintype "unspecified"))
      (node (ref "YIMAU2") (pin "2") (pinfunction "C_2") (pintype "unspecified"))
    )
    (net (code "101") (name "Net-(U12-(A<B)OUT)") (class "Default")
      (node (ref "U12") (pin "12") (pinfunction "(A<B)OUT_12") (pintype "unspecified"))
      (node (ref "U13") (pin "5") (pinfunction "(A<B)IN_5") (pintype "unspecified"))
    )
    (net (code "102") (name "Net-(U12-(A=B)OUT)") (class "Default")
      (node (ref "U12") (pin "3") (pinfunction "(A=B)OUT_3") (pintype "unspecified"))
      (node (ref "U13") (pin "6") (pinfunction "(A=B)IN_6") (pintype "unspecified"))
    )
    (net (code "103") (name "Net-(U12-(A>B)OUT)") (class "Default")
      (node (ref "U12") (pin "13") (pinfunction "(A>B)OUT_13") (pintype "unspecified"))
      (node (ref "U13") (pin "4") (pinfunction "(A>B)IN_4") (pintype "unspecified"))
    )
    (net (code "104") (name "Net-(U12-A0)") (class "Default")
      (node (ref "U12") (pin "10") (pinfunction "A0_10") (pintype "unspecified"))
      (node (ref "U3") (pin "13") (pinfunction "4B_13") (pintype "unspecified"))
      (node (ref "U5") (pin "14") (pinfunction "QA_14") (pintype "unspecified"))
      (node (ref "YIMAU4") (pin "7") (pinfunction "A_7") (pintype "unspecified"))
    )
    (net (code "105") (name "Net-(U12-A1)") (class "Default")
      (node (ref "U12") (pin "7") (pinfunction "A1_7") (pintype "unspecified"))
      (node (ref "U5") (pin "13") (pinfunction "QB_13") (pintype "unspecified"))
      (node (ref "YIMAU4") (pin "1") (pinfunction "B_1") (pintype "unspecified"))
    )
    (net (code "106") (name "Net-(U12-A2)") (class "Default")
      (node (ref "U12") (pin "2") (pinfunction "A2_2") (pintype "unspecified"))
      (node (ref "U3") (pin "12") (pinfunction "4A_12") (pintype "unspecified"))
      (node (ref "U5") (pin "12") (pinfunction "QC_12") (pintype "unspecified"))
      (node (ref "YIMAU4") (pin "2") (pinfunction "C_2") (pintype "unspecified"))
    )
    (net (code "107") (name "Net-(U12-B0)") (class "Default")
      (node (ref "U12") (pin "11") (pinfunction "B0_11") (pintype "unspecified"))
      (node (ref "U19") (pin "14") (pinfunction "QA_14") (pintype "unspecified"))
      (node (ref "YIMAU10") (pin "7") (pinfunction "A_7") (pintype "unspecified"))
    )
    (net (code "108") (name "Net-(U12-B1)") (class "Default")
      (node (ref "U12") (pin "9") (pinfunction "B1_9") (pintype "unspecified"))
      (node (ref "U19") (pin "13") (pinfunction "QB_13") (pintype "unspecified"))
      (node (ref "U22") (pin "13") (pinfunction "4B_13") (pintype "unspecified"))
      (node (ref "YIMAU10") (pin "1") (pinfunction "B_1") (pintype "unspecified"))
    )
    (net (code "109") (name "Net-(U12-B2)") (class "Default")
      (node (ref "U12") (pin "1") (pinfunction "B2_1") (pintype "unspecified"))
      (node (ref "U19") (pin "12") (pinfunction "QC_12") (pintype "unspecified"))
      (node (ref "U22") (pin "12") (pinfunction "4A_12") (pintype "unspecified"))
      (node (ref "YIMAU10") (pin "2") (pinfunction "C_2") (pintype "unspecified"))
    )
    (net (code "110") (name "Net-(U13-(A=B)OUT)") (class "Default")
      (node (ref "U13") (pin "3") (pinfunction "(A=B)OUT_3") (pintype "unspecified"))
      (node (ref "U17") (pin "13") (pinfunction "4B_13") (pintype "unspecified"))
    )
    (net (code "111") (name "Net-(U13-A1)") (class "Default")
      (node (ref "U13") (pin "7") (pinfunction "A1_7") (pintype "unspecified"))
      (node (ref "U6") (pin "13") (pinfunction "QB_13") (pintype "unspecified"))
      (node (ref "YIMAU3") (pin "1") (pinfunction "B_1") (pintype "unspecified"))
    )
    (net (code "112") (name "Net-(U13-A2)") (class "Default")
      (node (ref "U13") (pin "2") (pinfunction "A2_2") (pintype "unspecified"))
      (node (ref "U6") (pin "12") (pinfunction "QC_12") (pintype "unspecified"))
      (node (ref "YIMAU3") (pin "2") (pinfunction "C_2") (pintype "unspecified"))
    )
    (net (code "113") (name "Net-(U13-A3)") (class "Default")
      (node (ref "U13") (pin "15") (pinfunction "A3_15") (pintype "unspecified"))
      (node (ref "U3") (pin "10") (pinfunction "3B_10") (pintype "unspecified"))
      (node (ref "U6") (pin "11") (pinfunction "QD_11") (pintype "unspecified"))
      (node (ref "YIMAU3") (pin "6") (pinfunction "D_6") (pintype "unspecified"))
    )
    (net (code "114") (name "Net-(U13-B0)") (class "Default")
      (node (ref "U13") (pin "11") (pinfunction "B0_11") (pintype "unspecified"))
      (node (ref "U20") (pin "14") (pinfunction "QA_14") (pintype "unspecified"))
      (node (ref "YIMAU9") (pin "7") (pinfunction "A_7") (pintype "unspecified"))
    )
    (net (code "115") (name "Net-(U13-B1)") (class "Default")
      (node (ref "U13") (pin "9") (pinfunction "B1_9") (pintype "unspecified"))
      (node (ref "U20") (pin "13") (pinfunction "QB_13") (pintype "unspecified"))
      (node (ref "YIMAU9") (pin "1") (pinfunction "B_1") (pintype "unspecified"))
    )
    (net (code "116") (name "Net-(U13-B2)") (class "Default")
      (node (ref "U13") (pin "1") (pinfunction "B2_1") (pintype "unspecified"))
      (node (ref "U20") (pin "12") (pinfunction "QC_12") (pintype "unspecified"))
      (node (ref "YIMAU9") (pin "2") (pinfunction "C_2") (pintype "unspecified"))
    )
    (net (code "117") (name "Net-(U13-B3)") (class "Default")
      (node (ref "U13") (pin "14") (pinfunction "B3_14") (pintype "unspecified"))
      (node (ref "U20") (pin "11") (pinfunction "QD_11") (pintype "unspecified"))
      (node (ref "YIMAU9") (pin "6") (pinfunction "D_6") (pintype "unspecified"))
    )
    (net (code "118") (name "Net-(U14-(A<B)OUT)") (class "Default")
      (node (ref "U14") (pin "12") (pinfunction "(A<B)OUT_12") (pintype "unspecified"))
      (node (ref "U15") (pin "5") (pinfunction "(A<B)IN_5") (pintype "unspecified"))
    )
    (net (code "119") (name "Net-(U14-(A=B)OUT)") (class "Default")
      (node (ref "U14") (pin "3") (pinfunction "(A=B)OUT_3") (pintype "unspecified"))
      (node (ref "U15") (pin "6") (pinfunction "(A=B)IN_6") (pintype "unspecified"))
    )
    (net (code "120") (name "Net-(U14-(A>B)OUT)") (class "Default")
      (node (ref "U14") (pin "13") (pinfunction "(A>B)OUT_13") (pintype "unspecified"))
      (node (ref "U15") (pin "4") (pinfunction "(A>B)IN_4") (pintype "unspecified"))
    )
    (net (code "121") (name "Net-(U14-B0)") (class "Default")
      (node (ref "U14") (pin "11") (pinfunction "B0_11") (pintype "unspecified"))
      (node (ref "U18") (pin "14") (pinfunction "QA_14") (pintype "unspecified"))
      (node (ref "YIMAU7") (pin "7") (pinfunction "A_7") (pintype "unspecified"))
    )
    (net (code "122") (name "Net-(U14-B1)") (class "Default")
      (node (ref "U14") (pin "9") (pinfunction "B1_9") (pintype "unspecified"))
      (node (ref "U18") (pin "13") (pinfunction "QB_13") (pintype "unspecified"))
      (node (ref "U22") (pin "2") (pinfunction "1B_2") (pintype "unspecified"))
      (node (ref "YIMAU7") (pin "1") (pinfunction "B_1") (pintype "unspecified"))
    )
    (net (code "123") (name "Net-(U15-(A=B)OUT)") (class "Default")
      (node (ref "U15") (pin "3") (pinfunction "(A=B)OUT_3") (pintype "unspecified"))
      (node (ref "U17") (pin "12") (pinfunction "4A_12") (pintype "unspecified"))
    )
    (net (code "124") (name "Net-(U15-A0)") (class "Default")
      (node (ref "U15") (pin "10") (pinfunction "A0_10") (pintype "unspecified"))
      (node (ref "U16") (pin "1") (pinfunction "1A_1") (pintype "unspecified"))
      (node (ref "U16") (pin "13") (pinfunction "4B_13") (pintype "unspecified"))
      (node (ref "U4") (pin "14") (pinfunction "QA_14") (pintype "unspecified"))
      (node (ref "YIMAU5") (pin "7") (pinfunction "A_7") (pintype "unspecified"))
    )
    (net (code "125") (name "Net-(U15-A1)") (class "Default")
      (node (ref "U15") (pin "7") (pinfunction "A1_7") (pintype "unspecified"))
      (node (ref "U16") (pin "2") (pinfunction "1B_2") (pintype "unspecified"))
      (node (ref "U4") (pin "13") (pinfunction "QB_13") (pintype "unspecified"))
      (node (ref "YIMAU5") (pin "1") (pinfunction "B_1") (pintype "unspecified"))
    )
    (net (code "126") (name "Net-(U15-A2)") (class "Default")
      (node (ref "U15") (pin "2") (pinfunction "A2_2") (pintype "unspecified"))
      (node (ref "U4") (pin "12") (pinfunction "QC_12") (pintype "unspecified"))
      (node (ref "YIMAU5") (pin "2") (pinfunction "C_2") (pintype "unspecified"))
    )
    (net (code "127") (name "Net-(U15-A3)") (class "Default")
      (node (ref "U15") (pin "15") (pinfunction "A3_15") (pintype "unspecified"))
      (node (ref "U16") (pin "12") (pinfunction "4A_12") (pintype "unspecified"))
      (node (ref "U4") (pin "11") (pinfunction "QD_11") (pintype "unspecified"))
      (node (ref "YIMAU5") (pin "6") (pinfunction "D_6") (pintype "unspecified"))
    )
    (net (code "128") (name "Net-(U15-B0)") (class "Default")
      (node (ref "U15") (pin "11") (pinfunction "B0_11") (pintype "unspecified"))
      (node (ref "U9") (pin "14") (pinfunction "QA_14") (pintype "unspecified"))
      (node (ref "YIMAU8") (pin "7") (pinfunction "A_7") (pintype "unspecified"))
    )
    (net (code "129") (name "Net-(U15-B1)") (class "Default")
      (node (ref "U15") (pin "9") (pinfunction "B1_9") (pintype "unspecified"))
      (node (ref "U9") (pin "13") (pinfunction "QB_13") (pintype "unspecified"))
      (node (ref "YIMAU8") (pin "1") (pinfunction "B_1") (pintype "unspecified"))
    )
    (net (code "130") (name "Net-(U15-B2)") (class "Default")
      (node (ref "U15") (pin "1") (pinfunction "B2_1") (pintype "unspecified"))
      (node (ref "U22") (pin "1") (pinfunction "1A_1") (pintype "unspecified"))
      (node (ref "U9") (pin "12") (pinfunction "QC_12") (pintype "unspecified"))
      (node (ref "YIMAU8") (pin "2") (pinfunction "C_2") (pintype "unspecified"))
    )
    (net (code "131") (name "Net-(U15-B3)") (class "Default")
      (node (ref "U15") (pin "14") (pinfunction "B3_14") (pintype "unspecified"))
      (node (ref "U9") (pin "11") (pinfunction "QD_11") (pintype "unspecified"))
      (node (ref "YIMAU8") (pin "6") (pinfunction "D_6") (pintype "unspecified"))
    )
    (net (code "132") (name "Net-(U16-1Y)") (class "Default")
      (node (ref "U16") (pin "3") (pinfunction "1Y_3") (pintype "unspecified"))
      (node (ref "U16") (pin "4") (pinfunction "2A_4") (pintype "unspecified"))
    )
    (net (code "133") (name "Net-(U16-2Y)") (class "Default")
      (node (ref "U16") (pin "6") (pinfunction "2Y_6") (pintype "unspecified"))
      (node (ref "U2") (pin "4") (pinfunction "2A_4") (pintype "unspecified"))
    )
    (net (code "134") (name "Net-(U16-3B)") (class "Default")
      (node (ref "U16") (pin "10") (pinfunction "3B_10") (pintype "unspecified"))
      (node (ref "U16") (pin "11") (pinfunction "4Y_11") (pintype "unspecified"))
    )
    (net (code "135") (name "Net-(U17-1A)") (class "Default")
      (node (ref "U17") (pin "1") (pinfunction "1A_1") (pintype "unspecified"))
      (node (ref "U2") (pin "10") (pinfunction "3B_10") (pintype "unspecified"))
      (node (ref "U3") (pin "11") (pinfunction "4Y_11") (pintype "unspecified"))
    )
    (net (code "136") (name "Net-(U17-1B)") (class "Default")
      (node (ref "U17") (pin "2") (pinfunction "1B_2") (pintype "unspecified"))
      (node (ref "U2") (pin "13") (pinfunction "4B_13") (pintype "unspecified"))
      (node (ref "U3") (pin "8") (pinfunction "3Y_8") (pintype "unspecified"))
    )
    (net (code "137") (name "Net-(U17-1Y)") (class "Default")
      (node (ref "U17") (pin "3") (pinfunction "1Y_3") (pintype "unspecified"))
      (node (ref "U17") (pin "4") (pinfunction "2A_4") (pintype "unspecified"))
    )
    (net (code "138") (name "Net-(U17-2B)") (class "Default")
      (node (ref "U17") (pin "5") (pinfunction "2B_5") (pintype "unspecified"))
      (node (ref "U2") (pin "1") (pinfunction "1A_1") (pintype "unspecified"))
      (node (ref "U3") (pin "6") (pinfunction "2Y_6") (pintype "unspecified"))
    )
    (net (code "139") (name "Net-(U17-2Y)") (class "Default")
      (node (ref "BUZZER1") (pin "+") (pinfunction "+_+") (pintype "unspecified"))
      (node (ref "U17") (pin "6") (pinfunction "2Y_6") (pintype "unspecified"))
    )
    (net (code "140") (name "Net-(U18-CLK)") (class "Default")
      (node (ref "U18") (pin "2") (pinfunction "CLK_2") (pintype "unspecified"))
      (node (ref "U23") (pin "6") (pinfunction "3Y_6") (pintype "unspecified"))
    )
    (net (code "141") (name "Net-(U18-CLR)") (class "Default")
      (node (ref "U18") (pin "1") (pinfunction "CLR_1") (pintype "unspecified"))
      (node (ref "U22") (pin "3") (pinfunction "1Y_3") (pintype "unspecified"))
      (node (ref "U9") (pin "1") (pinfunction "CLR_1") (pintype "unspecified"))
    )
    (net (code "142") (name "Net-(U18-QC)") (class "Default")
      (node (ref "U18") (pin "12") (pinfunction "QC_12") (pintype "unspecified"))
      (node (ref "YIMAU7") (pin "2") (pinfunction "C_2") (pintype "unspecified"))
    )
    (net (code "143") (name "Net-(U18-QD)") (class "Default")
      (node (ref "U18") (pin "11") (pinfunction "QD_11") (pintype "unspecified"))
      (node (ref "YIMAU7") (pin "6") (pinfunction "D_6") (pintype "unspecified"))
    )
    (net (code "144") (name "Net-(U19-CLK)") (class "Default")
      (node (ref "U19") (pin "2") (pinfunction "CLK_2") (pintype "unspecified"))
      (node (ref "U23") (pin "2") (pinfunction "1Y_2") (pintype "unspecified"))
    )
    (net (code "145") (name "Net-(U19-CLR)") (class "Default")
      (node (ref "U19") (pin "1") (pinfunction "CLR_1") (pintype "unspecified"))
      (node (ref "U22") (pin "11") (pinfunction "4Y_11") (pintype "unspecified"))
    )
    (net (code "146") (name "Net-(U19-QD)") (class "Default")
      (node (ref "U19") (pin "11") (pinfunction "QD_11") (pintype "unspecified"))
      (node (ref "YIMAU10") (pin "6") (pinfunction "D_6") (pintype "unspecified"))
    )
    (net (code "147") (name "Net-(U20-CLK)") (class "Default")
      (node (ref "J2") (pin "2") (pinfunction "2_2") (pintype "unspecified"))
      (node (ref "U20") (pin "2") (pinfunction "CLK_2") (pintype "unspecified"))
    )
    (net (code "148") (name "Net-(U20-RCO)") (class "Default")
      (node (ref "U20") (pin "15") (pinfunction "RCO_15") (pintype "unspecified"))
      (node (ref "U23") (pin "1") (pinfunction "1A_1") (pintype "unspecified"))
    )
    (net (code "149") (name "Net-(U21-CONT)") (class "Default")
      (node (ref "C2") (pin "1") (pinfunction "1_1") (pintype "unspecified"))
      (node (ref "U21") (pin "5") (pinfunction "CONT_5") (pintype "unspecified"))
    )
    (net (code "150") (name "Net-(U21-DISCH)") (class "Default")
      (node (ref "R1") (pin "1") (pinfunction "1_1") (pintype "input"))
      (node (ref "R2") (pin "1") (pinfunction "1_1") (pintype "input"))
      (node (ref "U21") (pin "7") (pinfunction "DISCH_7") (pintype "unspecified"))
    )
    (net (code "151") (name "Net-(U21-THRES)") (class "Default")
      (node (ref "C1") (pin "1") (pinfunction "1_1") (pintype "unspecified"))
      (node (ref "R2") (pin "2") (pinfunction "2_2") (pintype "input"))
      (node (ref "U21") (pin "2") (pinfunction "TRIG_2") (pintype "unspecified"))
      (node (ref "U21") (pin "6") (pinfunction "THRES_6") (pintype "unspecified"))
    )
    (net (code "152") (name "Net-(U23-3A)") (class "Default")
      (node (ref "U23") (pin "5") (pinfunction "3A_5") (pintype "unspecified"))
      (node (ref "U9") (pin "15") (pinfunction "RCO_15") (pintype "unspecified"))
    )
    (net (code "153") (name "VCC") (class "Default")
      (node (ref "SEG1") (pin "3") (pinfunction "V1_3") (pintype "unspecified"))
      (node (ref "SEG1") (pin "8") (pinfunction "V2_8") (pintype "unspecified"))
      (node (ref "SEG10") (pin "3") (pinfunction "V1_3") (pintype "unspecified"))
      (node (ref "SEG10") (pin "8") (pinfunction "V2_8") (pintype "unspecified"))
      (node (ref "SEG2") (pin "3") (pinfunction "V1_3") (pintype "unspecified"))
      (node (ref "SEG2") (pin "8") (pinfunction "V2_8") (pintype "unspecified"))
      (node (ref "SEG3") (pin "3") (pinfunction "V1_3") (pintype "unspecified"))
      (node (ref "SEG3") (pin "8") (pinfunction "V2_8") (pintype "unspecified"))
      (node (ref "SEG4") (pin "3") (pinfunction "V1_3") (pintype "unspecified"))
      (node (ref "SEG4") (pin "8") (pinfunction "V2_8") (pintype "unspecified"))
      (node (ref "SEG5") (pin "3") (pinfunction "V1_3") (pintype "unspecified"))
      (node (ref "SEG5") (pin "8") (pinfunction "V2_8") (pintype "unspecified"))
      (node (ref "SEG6") (pin "3") (pinfunction "V1_3") (pintype "unspecified"))
      (node (ref "SEG6") (pin "8") (pinfunction "V2_8") (pintype "unspecified"))
      (node (ref "SEG7") (pin "3") (pinfunction "V1_3") (pintype "unspecified"))
      (node (ref "SEG7") (pin "8") (pinfunction "V2_8") (pintype "unspecified"))
      (node (ref "SEG8") (pin "3") (pinfunction "V1_3") (pintype "unspecified"))
      (node (ref "SEG8") (pin "8") (pinfunction "V2_8") (pintype "unspecified"))
      (node (ref "SEG9") (pin "3") (pinfunction "V1_3") (pintype "unspecified"))
      (node (ref "SEG9") (pin "8") (pinfunction "V2_8") (pintype "unspecified"))
      (node (ref "U1") (pin "1") (pinfunction "CLR_1") (pintype "unspecified"))
      (node (ref "U1") (pin "16") (pinfunction "VCC_16") (pintype "unspecified"))
      (node (ref "U10") (pin "14") (pinfunction "VCC_14") (pintype "unspecified"))
      (node (ref "U11") (pin "14") (pinfunction "VDD_14") (pintype "unspecified"))
      (node (ref "U12") (pin "16") (pinfunction "VDD_16") (pintype "unspecified"))
      (node (ref "U12") (pin "6") (pinfunction "(A=B)IN_6") (pintype "unspecified"))
      (node (ref "U13") (pin "10") (pinfunction "A0_10") (pintype "unspecified"))
      (node (ref "U13") (pin "16") (pinfunction "VDD_16") (pintype "unspecified"))
      (node (ref "U14") (pin "16") (pinfunction "VDD_16") (pintype "unspecified"))
      (node (ref "U14") (pin "6") (pinfunction "(A=B)IN_6") (pintype "unspecified"))
      (node (ref "U15") (pin "16") (pinfunction "VDD_16") (pintype "unspecified"))
      (node (ref "U16") (pin "14") (pinfunction "VCC_14") (pintype "unspecified"))
      (node (ref "U17") (pin "14") (pinfunction "VCC_14") (pintype "unspecified"))
      (node (ref "U18") (pin "10") (pinfunction "ENT_10") (pintype "unspecified"))
      (node (ref "U18") (pin "16") (pinfunction "VCC_16") (pintype "unspecified"))
      (node (ref "U18") (pin "7") (pinfunction "ENP_7") (pintype "unspecified"))
      (node (ref "U18") (pin "9") (pinfunction "LOAD_9") (pintype "unspecified"))
      (node (ref "U19") (pin "10") (pinfunction "ENT_10") (pintype "unspecified"))
      (node (ref "U19") (pin "16") (pinfunction "VCC_16") (pintype "unspecified"))
      (node (ref "U19") (pin "7") (pinfunction "ENP_7") (pintype "unspecified"))
      (node (ref "U19") (pin "9") (pinfunction "LOAD_9") (pintype "unspecified"))
      (node (ref "U2") (pin "14") (pinfunction "VCC_14") (pintype "unspecified"))
      (node (ref "U20") (pin "1") (pinfunction "CLR_1") (pintype "unspecified"))
      (node (ref "U20") (pin "10") (pinfunction "ENT_10") (pintype "unspecified"))
      (node (ref "U20") (pin "16") (pinfunction "VCC_16") (pintype "unspecified"))
      (node (ref "U20") (pin "7") (pinfunction "ENP_7") (pintype "unspecified"))
      (node (ref "U20") (pin "9") (pinfunction "LOAD_9") (pintype "unspecified"))
      (node (ref "U22") (pin "14") (pinfunction "VCC_14") (pintype "unspecified"))
      (node (ref "U23") (pin "14") (pinfunction "VCC_14") (pintype "unspecified"))
      (node (ref "U3") (pin "14") (pinfunction "VCC_14") (pintype "unspecified"))
      (node (ref "U3") (pin "9") (pinfunction "3A_9") (pintype "unspecified"))
      (node (ref "U4") (pin "1") (pinfunction "CLR_1") (pintype "unspecified"))
      (node (ref "U4") (pin "16") (pinfunction "VCC_16") (pintype "unspecified"))
      (node (ref "U5") (pin "1") (pinfunction "CLR_1") (pintype "unspecified"))
      (node (ref "U5") (pin "16") (pinfunction "VCC_16") (pintype "unspecified"))
      (node (ref "U6") (pin "1") (pinfunction "CLR_1") (pintype "unspecified"))
      (node (ref "U6") (pin "14") (pinfunction "QA_14") (pintype "unspecified"))
      (node (ref "U6") (pin "16") (pinfunction "VCC_16") (pintype "unspecified"))
      (node (ref "U7") (pin "1") (pinfunction "CLR_1") (pintype "unspecified"))
      (node (ref "U7") (pin "16") (pinfunction "VCC_16") (pintype "unspecified"))
      (node (ref "U8") (pin "1") (pinfunction "CLR_1") (pintype "unspecified"))
      (node (ref "U8") (pin "10") (pinfunction "ENT_10") (pintype "unspecified"))
      (node (ref "U8") (pin "16") (pinfunction "VCC_16") (pintype "unspecified"))
      (node (ref "U8") (pin "7") (pinfunction "ENP_7") (pintype "unspecified"))
      (node (ref "U8") (pin "9") (pinfunction "LOAD_9") (pintype "unspecified"))
      (node (ref "U9") (pin "10") (pinfunction "ENT_10") (pintype "unspecified"))
      (node (ref "U9") (pin "16") (pinfunction "VCC_16") (pintype "unspecified"))
      (node (ref "U9") (pin "7") (pinfunction "ENP_7") (pintype "unspecified"))
      (node (ref "U9") (pin "9") (pinfunction "LOAD_9") (pintype "unspecified"))
      (node (ref "YIMAU1") (pin "16") (pinfunction "VCC_16") (pintype "passive"))
      (node (ref "YIMAU1") (pin "3") (pinfunction "LT_3") (pintype "unspecified"))
      (node (ref "YIMAU1") (pin "4") (pinfunction "BIRBO_4") (pintype "bidirectional"))
      (node (ref "YIMAU1") (pin "5") (pinfunction "RBI_5") (pintype "unspecified"))
      (node (ref "YIMAU10") (pin "16") (pinfunction "VCC_16") (pintype "passive"))
      (node (ref "YIMAU10") (pin "3") (pinfunction "LT_3") (pintype "unspecified"))
      (node (ref "YIMAU10") (pin "4") (pinfunction "BIRBO_4") (pintype "bidirectional"))
      (node (ref "YIMAU10") (pin "5") (pinfunction "RBI_5") (pintype "unspecified"))
      (node (ref "YIMAU2") (pin "16") (pinfunction "VCC_16") (pintype "passive"))
      (node (ref "YIMAU2") (pin "3") (pinfunction "LT_3") (pintype "unspecified"))
      (node (ref "YIMAU2") (pin "4") (pinfunction "BIRBO_4") (pintype "bidirectional"))
      (node (ref "YIMAU2") (pin "5") (pinfunction "RBI_5") (pintype "unspecified"))
      (node (ref "YIMAU3") (pin "16") (pinfunction "VCC_16") (pintype "passive"))
      (node (ref "YIMAU3") (pin "3") (pinfunction "LT_3") (pintype "unspecified"))
      (node (ref "YIMAU3") (pin "4") (pinfunction "BIRBO_4") (pintype "bidirectional"))
      (node (ref "YIMAU3") (pin "5") (pinfunction "RBI_5") (pintype "unspecified"))
      (node (ref "YIMAU3") (pin "7") (pinfunction "A_7") (pintype "unspecified"))
      (node (ref "YIMAU4") (pin "16") (pinfunction "VCC_16") (pintype "passive"))
      (node (ref "YIMAU4") (pin "3") (pinfunction "LT_3") (pintype "unspecified"))
      (node (ref "YIMAU4") (pin "4") (pinfunction "BIRBO_4") (pintype "bidirectional"))
      (node (ref "YIMAU4") (pin "5") (pinfunction "RBI_5") (pintype "unspecified"))
      (node (ref "YIMAU5") (pin "16") (pinfunction "VCC_16") (pintype "passive"))
      (node (ref "YIMAU5") (pin "3") (pinfunction "LT_3") (pintype "unspecified"))
      (node (ref "YIMAU5") (pin "4") (pinfunction "BIRBO_4") (pintype "bidirectional"))
      (node (ref "YIMAU5") (pin "5") (pinfunction "RBI_5") (pintype "unspecified"))
      (node (ref "YIMAU6") (pin "16") (pinfunction "VCC_16") (pintype "passive"))
      (node (ref "YIMAU6") (pin "3") (pinfunction "LT_3") (pintype "unspecified"))
      (node (ref "YIMAU6") (pin "4") (pinfunction "BIRBO_4") (pintype "bidirectional"))
      (node (ref "YIMAU6") (pin "5") (pinfunction "RBI_5") (pintype "unspecified"))
      (node (ref "YIMAU7") (pin "16") (pinfunction "VCC_16") (pintype "passive"))
      (node (ref "YIMAU7") (pin "3") (pinfunction "LT_3") (pintype "unspecified"))
      (node (ref "YIMAU7") (pin "4") (pinfunction "BIRBO_4") (pintype "bidirectional"))
      (node (ref "YIMAU7") (pin "5") (pinfunction "RBI_5") (pintype "unspecified"))
      (node (ref "YIMAU8") (pin "16") (pinfunction "VCC_16") (pintype "passive"))
      (node (ref "YIMAU8") (pin "3") (pinfunction "LT_3") (pintype "unspecified"))
      (node (ref "YIMAU8") (pin "4") (pinfunction "BIRBO_4") (pintype "bidirectional"))
      (node (ref "YIMAU8") (pin "5") (pinfunction "RBI_5") (pintype "unspecified"))
      (node (ref "YIMAU9") (pin "16") (pinfunction "VCC_16") (pintype "passive"))
      (node (ref "YIMAU9") (pin "3") (pinfunction "LT_3") (pintype "unspecified"))
      (node (ref "YIMAU9") (pin "4") (pinfunction "BIRBO_4") (pintype "bidirectional"))
      (node (ref "YIMAU9") (pin "5") (pinfunction "RBI_5") (pintype "unspecified"))
    )
    (net (code "154") (name "VCC5V") (class "Default")
      (node (ref "R1") (pin "2") (pinfunction "2_2") (pintype "input"))
      (node (ref "U21") (pin "4") (pinfunction "RESET_4") (pintype "unspecified"))
      (node (ref "U21") (pin "8") (pinfunction "VCC_8") (pintype "unspecified"))
    )
    (net (code "155") (name "unconnected-(SEG1-DP-Pad5)") (class "Default")
      (node (ref "SEG1") (pin "5") (pinfunction "DP_5") (pintype "unspecified"))
    )
    (net (code "156") (name "unconnected-(SEG2-DP-Pad5)") (class "Default")
      (node (ref "SEG2") (pin "5") (pinfunction "DP_5") (pintype "unspecified"))
    )
    (net (code "157") (name "unconnected-(SEG3-DP-Pad5)") (class "Default")
      (node (ref "SEG3") (pin "5") (pinfunction "DP_5") (pintype "unspecified"))
    )
    (net (code "158") (name "unconnected-(SEG4-DP-Pad5)") (class "Default")
      (node (ref "SEG4") (pin "5") (pinfunction "DP_5") (pintype "unspecified"))
    )
    (net (code "159") (name "unconnected-(SEG5-DP-Pad5)") (class "Default")
      (node (ref "SEG5") (pin "5") (pinfunction "DP_5") (pintype "unspecified"))
    )
    (net (code "160") (name "unconnected-(SEG6-DP-Pad5)") (class "Default")
      (node (ref "SEG6") (pin "5") (pinfunction "DP_5") (pintype "unspecified"))
    )
    (net (code "161") (name "unconnected-(SEG7-DP-Pad5)") (class "Default")
      (node (ref "SEG7") (pin "5") (pinfunction "DP_5") (pintype "unspecified"))
    )
    (net (code "162") (name "unconnected-(SEG8-DP-Pad5)") (class "Default")
      (node (ref "SEG8") (pin "5") (pinfunction "DP_5") (pintype "unspecified"))
    )
    (net (code "163") (name "unconnected-(SEG9-DP-Pad5)") (class "Default")
      (node (ref "SEG9") (pin "5") (pinfunction "DP_5") (pintype "unspecified"))
    )
    (net (code "164") (name "unconnected-(SEG10-DP-Pad5)") (class "Default")
      (node (ref "SEG10") (pin "5") (pinfunction "DP_5") (pintype "unspecified"))
    )
    (net (code "165") (name "unconnected-(U1-A-Pad3)") (class "Default")
      (node (ref "U1") (pin "3") (pinfunction "A_3") (pintype "unspecified"))
    )
    (net (code "166") (name "unconnected-(U1-B-Pad4)") (class "Default")
      (node (ref "U1") (pin "4") (pinfunction "B_4") (pintype "unspecified"))
    )
    (net (code "167") (name "unconnected-(U1-C-Pad5)") (class "Default")
      (node (ref "U1") (pin "5") (pinfunction "C_5") (pintype "unspecified"))
    )
    (net (code "168") (name "unconnected-(U1-D-Pad6)") (class "Default")
      (node (ref "U1") (pin "6") (pinfunction "D_6") (pintype "unspecified"))
    )
    (net (code "169") (name "unconnected-(U1-RCO-Pad15)") (class "Default")
      (node (ref "U1") (pin "15") (pinfunction "RCO_15") (pintype "unspecified"))
    )
    (net (code "170") (name "unconnected-(U4-A-Pad3)") (class "Default")
      (node (ref "U4") (pin "3") (pinfunction "A_3") (pintype "unspecified"))
    )
    (net (code "171") (name "unconnected-(U4-B-Pad4)") (class "Default")
      (node (ref "U4") (pin "4") (pinfunction "B_4") (pintype "unspecified"))
    )
    (net (code "172") (name "unconnected-(U4-C-Pad5)") (class "Default")
      (node (ref "U4") (pin "5") (pinfunction "C_5") (pintype "unspecified"))
    )
    (net (code "173") (name "unconnected-(U4-D-Pad6)") (class "Default")
      (node (ref "U4") (pin "6") (pinfunction "D_6") (pintype "unspecified"))
    )
    (net (code "174") (name "unconnected-(U4-LOAD-Pad9)") (class "Default")
      (node (ref "U4") (pin "9") (pinfunction "LOAD_9") (pintype "unspecified"))
    )
    (net (code "175") (name "unconnected-(U4-RCO-Pad15)") (class "Default")
      (node (ref "U4") (pin "15") (pinfunction "RCO_15") (pintype "unspecified"))
    )
    (net (code "176") (name "unconnected-(U5-A-Pad3)") (class "Default")
      (node (ref "U5") (pin "3") (pinfunction "A_3") (pintype "unspecified"))
    )
    (net (code "177") (name "unconnected-(U5-B-Pad4)") (class "Default")
      (node (ref "U5") (pin "4") (pinfunction "B_4") (pintype "unspecified"))
    )
    (net (code "178") (name "unconnected-(U5-C-Pad5)") (class "Default")
      (node (ref "U5") (pin "5") (pinfunction "C_5") (pintype "unspecified"))
    )
    (net (code "179") (name "unconnected-(U5-D-Pad6)") (class "Default")
      (node (ref "U5") (pin "6") (pinfunction "D_6") (pintype "unspecified"))
    )
    (net (code "180") (name "unconnected-(U5-RCO-Pad15)") (class "Default")
      (node (ref "U5") (pin "15") (pinfunction "RCO_15") (pintype "unspecified"))
    )
    (net (code "181") (name "unconnected-(U6-A-Pad3)") (class "Default")
      (node (ref "U6") (pin "3") (pinfunction "A_3") (pintype "unspecified"))
    )
    (net (code "182") (name "unconnected-(U6-B-Pad4)") (class "Default")
      (node (ref "U6") (pin "4") (pinfunction "B_4") (pintype "unspecified"))
    )
    (net (code "183") (name "unconnected-(U6-C-Pad5)") (class "Default")
      (node (ref "U6") (pin "5") (pinfunction "C_5") (pintype "unspecified"))
    )
    (net (code "184") (name "unconnected-(U6-D-Pad6)") (class "Default")
      (node (ref "U6") (pin "6") (pinfunction "D_6") (pintype "unspecified"))
    )
    (net (code "185") (name "unconnected-(U6-RCO-Pad15)") (class "Default")
      (node (ref "U6") (pin "15") (pinfunction "RCO_15") (pintype "unspecified"))
    )
    (net (code "186") (name "unconnected-(U7-A-Pad3)") (class "Default")
      (node (ref "U7") (pin "3") (pinfunction "A_3") (pintype "unspecified"))
    )
    (net (code "187") (name "unconnected-(U7-B-Pad4)") (class "Default")
      (node (ref "U7") (pin "4") (pinfunction "B_4") (pintype "unspecified"))
    )
    (net (code "188") (name "unconnected-(U7-C-Pad5)") (class "Default")
      (node (ref "U7") (pin "5") (pinfunction "C_5") (pintype "unspecified"))
    )
    (net (code "189") (name "unconnected-(U7-D-Pad6)") (class "Default")
      (node (ref "U7") (pin "6") (pinfunction "D_6") (pintype "unspecified"))
    )
    (net (code "190") (name "unconnected-(U7-RCO-Pad15)") (class "Default")
      (node (ref "U7") (pin "15") (pinfunction "RCO_15") (pintype "unspecified"))
    )
    (net (code "191") (name "unconnected-(U8-A-Pad3)") (class "Default")
      (node (ref "U8") (pin "3") (pinfunction "A_3") (pintype "unspecified"))
    )
    (net (code "192") (name "unconnected-(U8-B-Pad4)") (class "Default")
      (node (ref "U8") (pin "4") (pinfunction "B_4") (pintype "unspecified"))
    )
    (net (code "193") (name "unconnected-(U8-C-Pad5)") (class "Default")
      (node (ref "U8") (pin "5") (pinfunction "C_5") (pintype "unspecified"))
    )
    (net (code "194") (name "unconnected-(U8-D-Pad6)") (class "Default")
      (node (ref "U8") (pin "6") (pinfunction "D_6") (pintype "unspecified"))
    )
    (net (code "195") (name "unconnected-(U8-RCO-Pad15)") (class "Default")
      (node (ref "U8") (pin "15") (pinfunction "RCO_15") (pintype "unspecified"))
    )
    (net (code "196") (name "unconnected-(U9-A-Pad3)") (class "Default")
      (node (ref "U9") (pin "3") (pinfunction "A_3") (pintype "unspecified"))
    )
    (net (code "197") (name "unconnected-(U9-B-Pad4)") (class "Default")
      (node (ref "U9") (pin "4") (pinfunction "B_4") (pintype "unspecified"))
    )
    (net (code "198") (name "unconnected-(U9-C-Pad5)") (class "Default")
      (node (ref "U9") (pin "5") (pinfunction "C_5") (pintype "unspecified"))
    )
    (net (code "199") (name "unconnected-(U9-D-Pad6)") (class "Default")
      (node (ref "U9") (pin "6") (pinfunction "D_6") (pintype "unspecified"))
    )
    (net (code "200") (name "unconnected-(U10-4A-Pad9)") (class "Default")
      (node (ref "U10") (pin "9") (pinfunction "4A_9") (pintype "unspecified"))
    )
    (net (code "201") (name "unconnected-(U10-4Y-Pad8)") (class "Default")
      (node (ref "U10") (pin "8") (pinfunction "4Y_8") (pintype "unspecified"))
    )
    (net (code "202") (name "unconnected-(U10-5A-Pad11)") (class "Default")
      (node (ref "U10") (pin "11") (pinfunction "5A_11") (pintype "unspecified"))
    )
    (net (code "203") (name "unconnected-(U10-5Y-Pad10)") (class "Default")
      (node (ref "U10") (pin "10") (pinfunction "5Y_10") (pintype "unspecified"))
    )
    (net (code "204") (name "unconnected-(U10-6A-Pad13)") (class "Default")
      (node (ref "U10") (pin "13") (pinfunction "6A_13") (pintype "unspecified"))
    )
    (net (code "205") (name "unconnected-(U10-6Y-Pad12)") (class "Default")
      (node (ref "U10") (pin "12") (pinfunction "6Y_12") (pintype "unspecified"))
    )
    (net (code "206") (name "unconnected-(U11-A-Pad1)") (class "Default")
      (node (ref "U11") (pin "1") (pinfunction "A_1") (pintype "unspecified"))
    )
    (net (code "207") (name "unconnected-(U11-B-Pad2)") (class "Default")
      (node (ref "U11") (pin "2") (pinfunction "B_2") (pintype "unspecified"))
    )
    (net (code "208") (name "unconnected-(U11-C-Pad8)") (class "Default")
      (node (ref "U11") (pin "8") (pinfunction "C_8") (pintype "unspecified"))
    )
    (net (code "209") (name "unconnected-(U11-G-Pad13)") (class "Default")
      (node (ref "U11") (pin "13") (pinfunction "G_13") (pintype "unspecified"))
    )
    (net (code "210") (name "unconnected-(U11-H-Pad12)") (class "Default")
      (node (ref "U11") (pin "12") (pinfunction "H_12") (pintype "unspecified"))
    )
    (net (code "211") (name "unconnected-(U11-I-Pad11)") (class "Default")
      (node (ref "U11") (pin "11") (pinfunction "I_11") (pintype "unspecified"))
    )
    (net (code "212") (name "unconnected-(U11-J-Pad9)") (class "Default")
      (node (ref "U11") (pin "9") (pinfunction "J_9") (pintype "unspecified"))
    )
    (net (code "213") (name "unconnected-(U11-L-Pad10)") (class "Default")
      (node (ref "U11") (pin "10") (pinfunction "L_10") (pintype "unspecified"))
    )
    (net (code "214") (name "unconnected-(U12-VSS-Pad8)") (class "Default")
      (node (ref "U12") (pin "8") (pinfunction "VSS_8") (pintype "unspecified"))
    )
    (net (code "215") (name "unconnected-(U13-(A<B)OUT-Pad12)") (class "Default")
      (node (ref "U13") (pin "12") (pinfunction "(A<B)OUT_12") (pintype "unspecified"))
    )
    (net (code "216") (name "unconnected-(U13-(A>B)OUT-Pad13)") (class "Default")
      (node (ref "U13") (pin "13") (pinfunction "(A>B)OUT_13") (pintype "unspecified"))
    )
    (net (code "217") (name "unconnected-(U13-VSS-Pad8)") (class "Default")
      (node (ref "U13") (pin "8") (pinfunction "VSS_8") (pintype "unspecified"))
    )
    (net (code "218") (name "unconnected-(U15-(A<B)OUT-Pad12)") (class "Default")
      (node (ref "U15") (pin "12") (pinfunction "(A<B)OUT_12") (pintype "unspecified"))
    )
    (net (code "219") (name "unconnected-(U15-(A>B)OUT-Pad13)") (class "Default")
      (node (ref "U15") (pin "13") (pinfunction "(A>B)OUT_13") (pintype "unspecified"))
    )
    (net (code "220") (name "unconnected-(U17-3A-Pad9)") (class "Default")
      (node (ref "U17") (pin "9") (pinfunction "3A_9") (pintype "unspecified"))
    )
    (net (code "221") (name "unconnected-(U17-3B-Pad10)") (class "Default")
      (node (ref "U17") (pin "10") (pinfunction "3B_10") (pintype "unspecified"))
    )
    (net (code "222") (name "unconnected-(U17-3Y-Pad8)") (class "Default")
      (node (ref "U17") (pin "8") (pinfunction "3Y_8") (pintype "unspecified"))
    )
    (net (code "223") (name "unconnected-(U18-A-Pad3)") (class "Default")
      (node (ref "U18") (pin "3") (pinfunction "A_3") (pintype "unspecified"))
    )
    (net (code "224") (name "unconnected-(U18-B-Pad4)") (class "Default")
      (node (ref "U18") (pin "4") (pinfunction "B_4") (pintype "unspecified"))
    )
    (net (code "225") (name "unconnected-(U18-C-Pad5)") (class "Default")
      (node (ref "U18") (pin "5") (pinfunction "C_5") (pintype "unspecified"))
    )
    (net (code "226") (name "unconnected-(U18-D-Pad6)") (class "Default")
      (node (ref "U18") (pin "6") (pinfunction "D_6") (pintype "unspecified"))
    )
    (net (code "227") (name "unconnected-(U18-RCO-Pad15)") (class "Default")
      (node (ref "U18") (pin "15") (pinfunction "RCO_15") (pintype "unspecified"))
    )
    (net (code "228") (name "unconnected-(U19-A-Pad3)") (class "Default")
      (node (ref "U19") (pin "3") (pinfunction "A_3") (pintype "unspecified"))
    )
    (net (code "229") (name "unconnected-(U19-B-Pad4)") (class "Default")
      (node (ref "U19") (pin "4") (pinfunction "B_4") (pintype "unspecified"))
    )
    (net (code "230") (name "unconnected-(U19-C-Pad5)") (class "Default")
      (node (ref "U19") (pin "5") (pinfunction "C_5") (pintype "unspecified"))
    )
    (net (code "231") (name "unconnected-(U19-D-Pad6)") (class "Default")
      (node (ref "U19") (pin "6") (pinfunction "D_6") (pintype "unspecified"))
    )
    (net (code "232") (name "unconnected-(U19-RCO-Pad15)") (class "Default")
      (node (ref "U19") (pin "15") (pinfunction "RCO_15") (pintype "unspecified"))
    )
    (net (code "233") (name "unconnected-(U20-A-Pad3)") (class "Default")
      (node (ref "U20") (pin "3") (pinfunction "A_3") (pintype "unspecified"))
    )
    (net (code "234") (name "unconnected-(U20-B-Pad4)") (class "Default")
      (node (ref "U20") (pin "4") (pinfunction "B_4") (pintype "unspecified"))
    )
    (net (code "235") (name "unconnected-(U20-C-Pad5)") (class "Default")
      (node (ref "U20") (pin "5") (pinfunction "C_5") (pintype "unspecified"))
    )
    (net (code "236") (name "unconnected-(U20-D-Pad6)") (class "Default")
      (node (ref "U20") (pin "6") (pinfunction "D_6") (pintype "unspecified"))
    )
    (net (code "237") (name "unconnected-(U22-2A-Pad4)") (class "Default")
      (node (ref "U22") (pin "4") (pinfunction "2A_4") (pintype "unspecified"))
    )
    (net (code "238") (name "unconnected-(U22-2B-Pad5)") (class "Default")
      (node (ref "U22") (pin "5") (pinfunction "2B_5") (pintype "unspecified"))
    )
    (net (code "239") (name "unconnected-(U22-2Y-Pad6)") (class "Default")
      (node (ref "U22") (pin "6") (pinfunction "2Y_6") (pintype "unspecified"))
    )
    (net (code "240") (name "unconnected-(U22-3A-Pad9)") (class "Default")
      (node (ref "U22") (pin "9") (pinfunction "3A_9") (pintype "unspecified"))
    )
    (net (code "241") (name "unconnected-(U22-3B-Pad10)") (class "Default")
      (node (ref "U22") (pin "10") (pinfunction "3B_10") (pintype "unspecified"))
    )
    (net (code "242") (name "unconnected-(U22-3Y-Pad8)") (class "Default")
      (node (ref "U22") (pin "8") (pinfunction "3Y_8") (pintype "unspecified"))
    )
    (net (code "243") (name "unconnected-(U23-2A-Pad3)") (class "Default")
      (node (ref "U23") (pin "3") (pinfunction "2A_3") (pintype "unspecified"))
    )
    (net (code "244") (name "unconnected-(U23-2Y-Pad4)") (class "Default")
      (node (ref "U23") (pin "4") (pinfunction "2Y_4") (pintype "unspecified"))
    )
    (net (code "245") (name "unconnected-(U23-4A-Pad9)") (class "Default")
      (node (ref "U23") (pin "9") (pinfunction "4A_9") (pintype "unspecified"))
    )
    (net (code "246") (name "unconnected-(U23-4Y-Pad8)") (class "Default")
      (node (ref "U23") (pin "8") (pinfunction "4Y_8") (pintype "unspecified"))
    )
    (net (code "247") (name "unconnected-(U23-5A-Pad11)") (class "Default")
      (node (ref "U23") (pin "11") (pinfunction "5A_11") (pintype "unspecified"))
    )
    (net (code "248") (name "unconnected-(U23-5Y-Pad10)") (class "Default")
      (node (ref "U23") (pin "10") (pinfunction "5Y_10") (pintype "unspecified"))
    )
    (net (code "249") (name "unconnected-(U23-6A-Pad13)") (class "Default")
      (node (ref "U23") (pin "13") (pinfunction "6A_13") (pintype "unspecified"))
    )
    (net (code "250") (name "unconnected-(U23-6Y-Pad12)") (class "Default")
      (node (ref "U23") (pin "12") (pinfunction "6Y_12") (pintype "unspecified"))
    )
  )
)
